# Solarregler.net
KiCad netlist of a schematic drawn in EAGLE
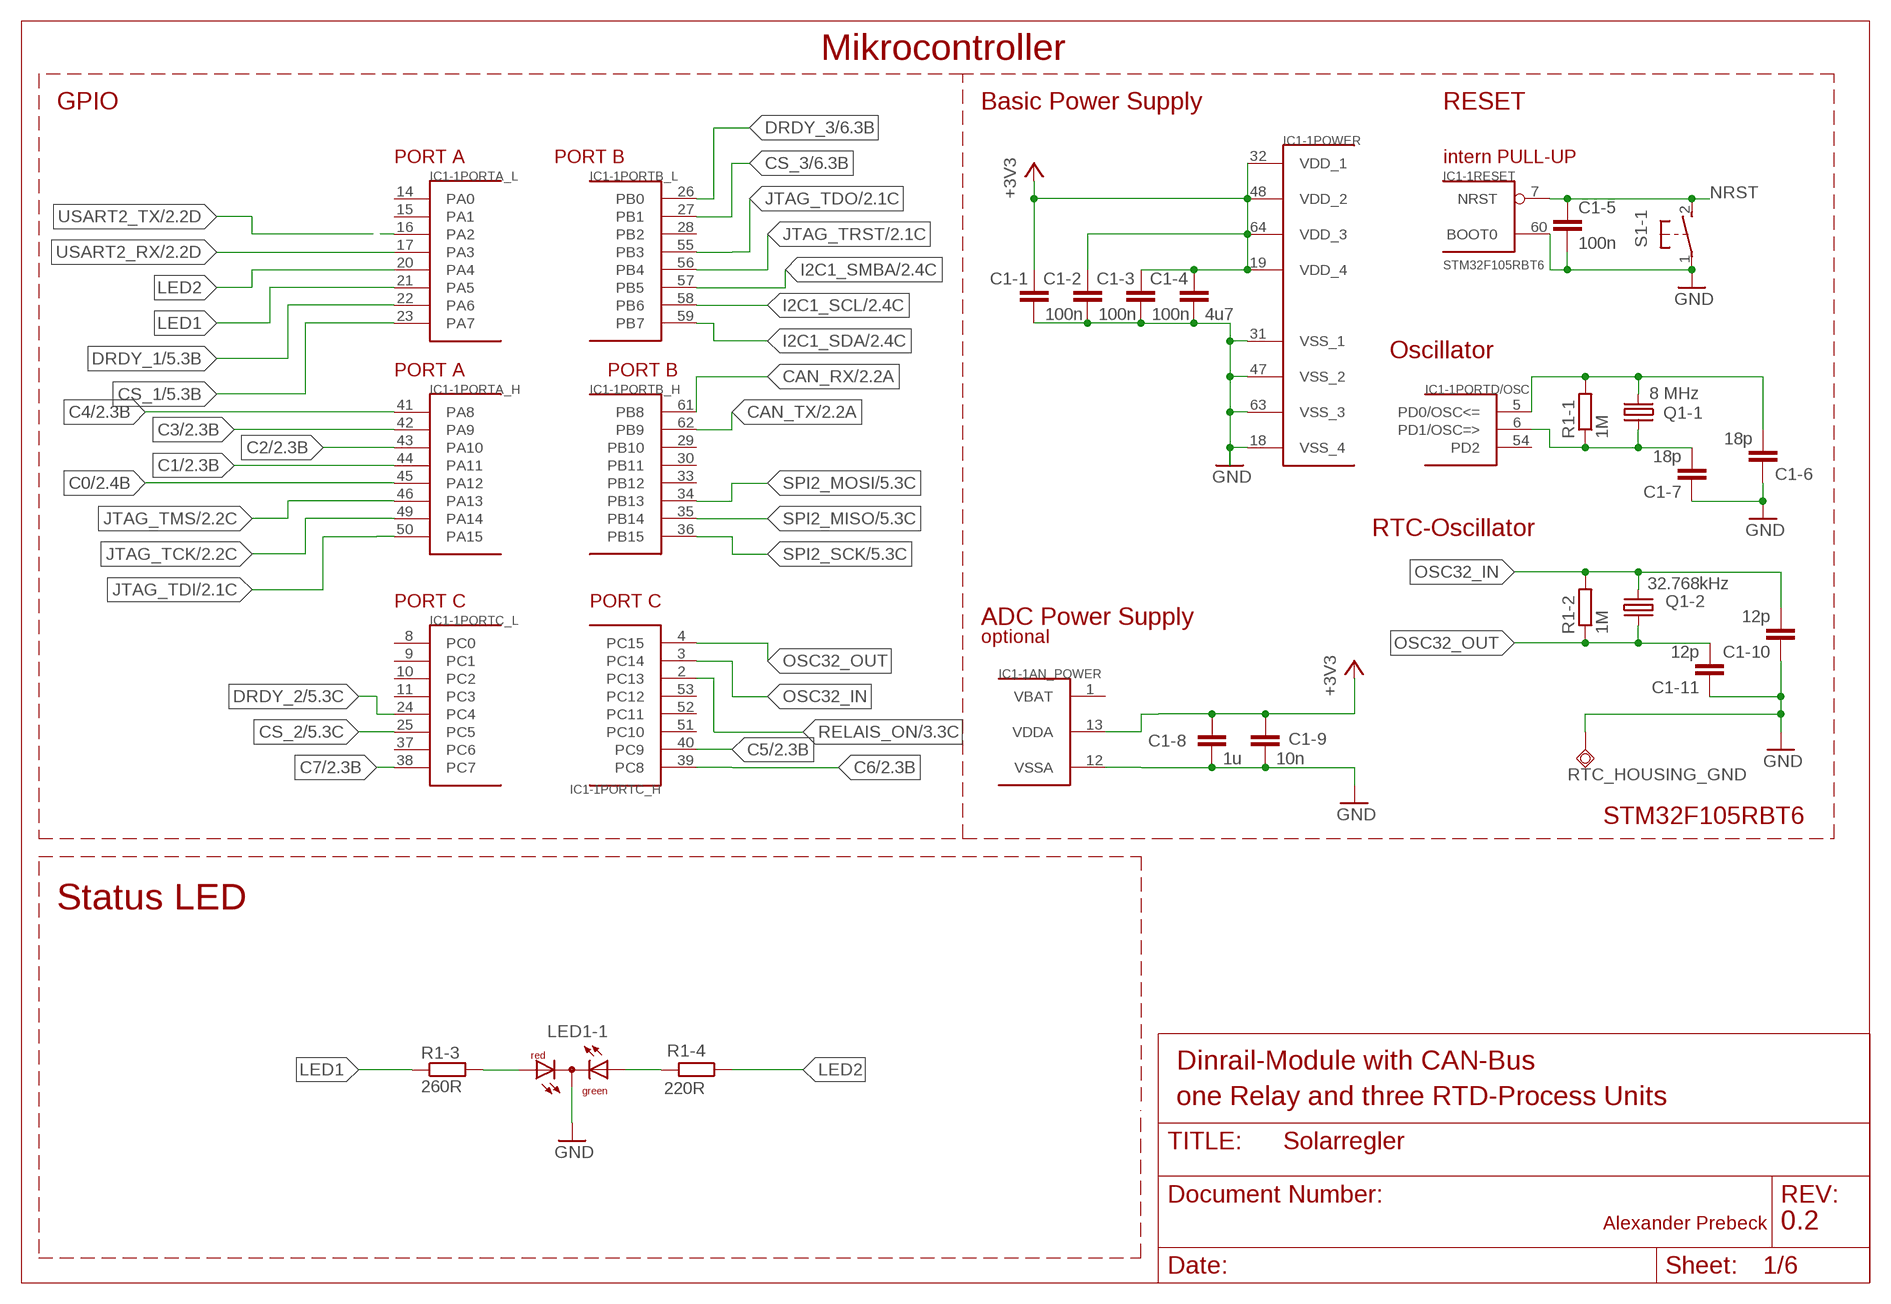
[diagram p0: schematic, sheet 1]
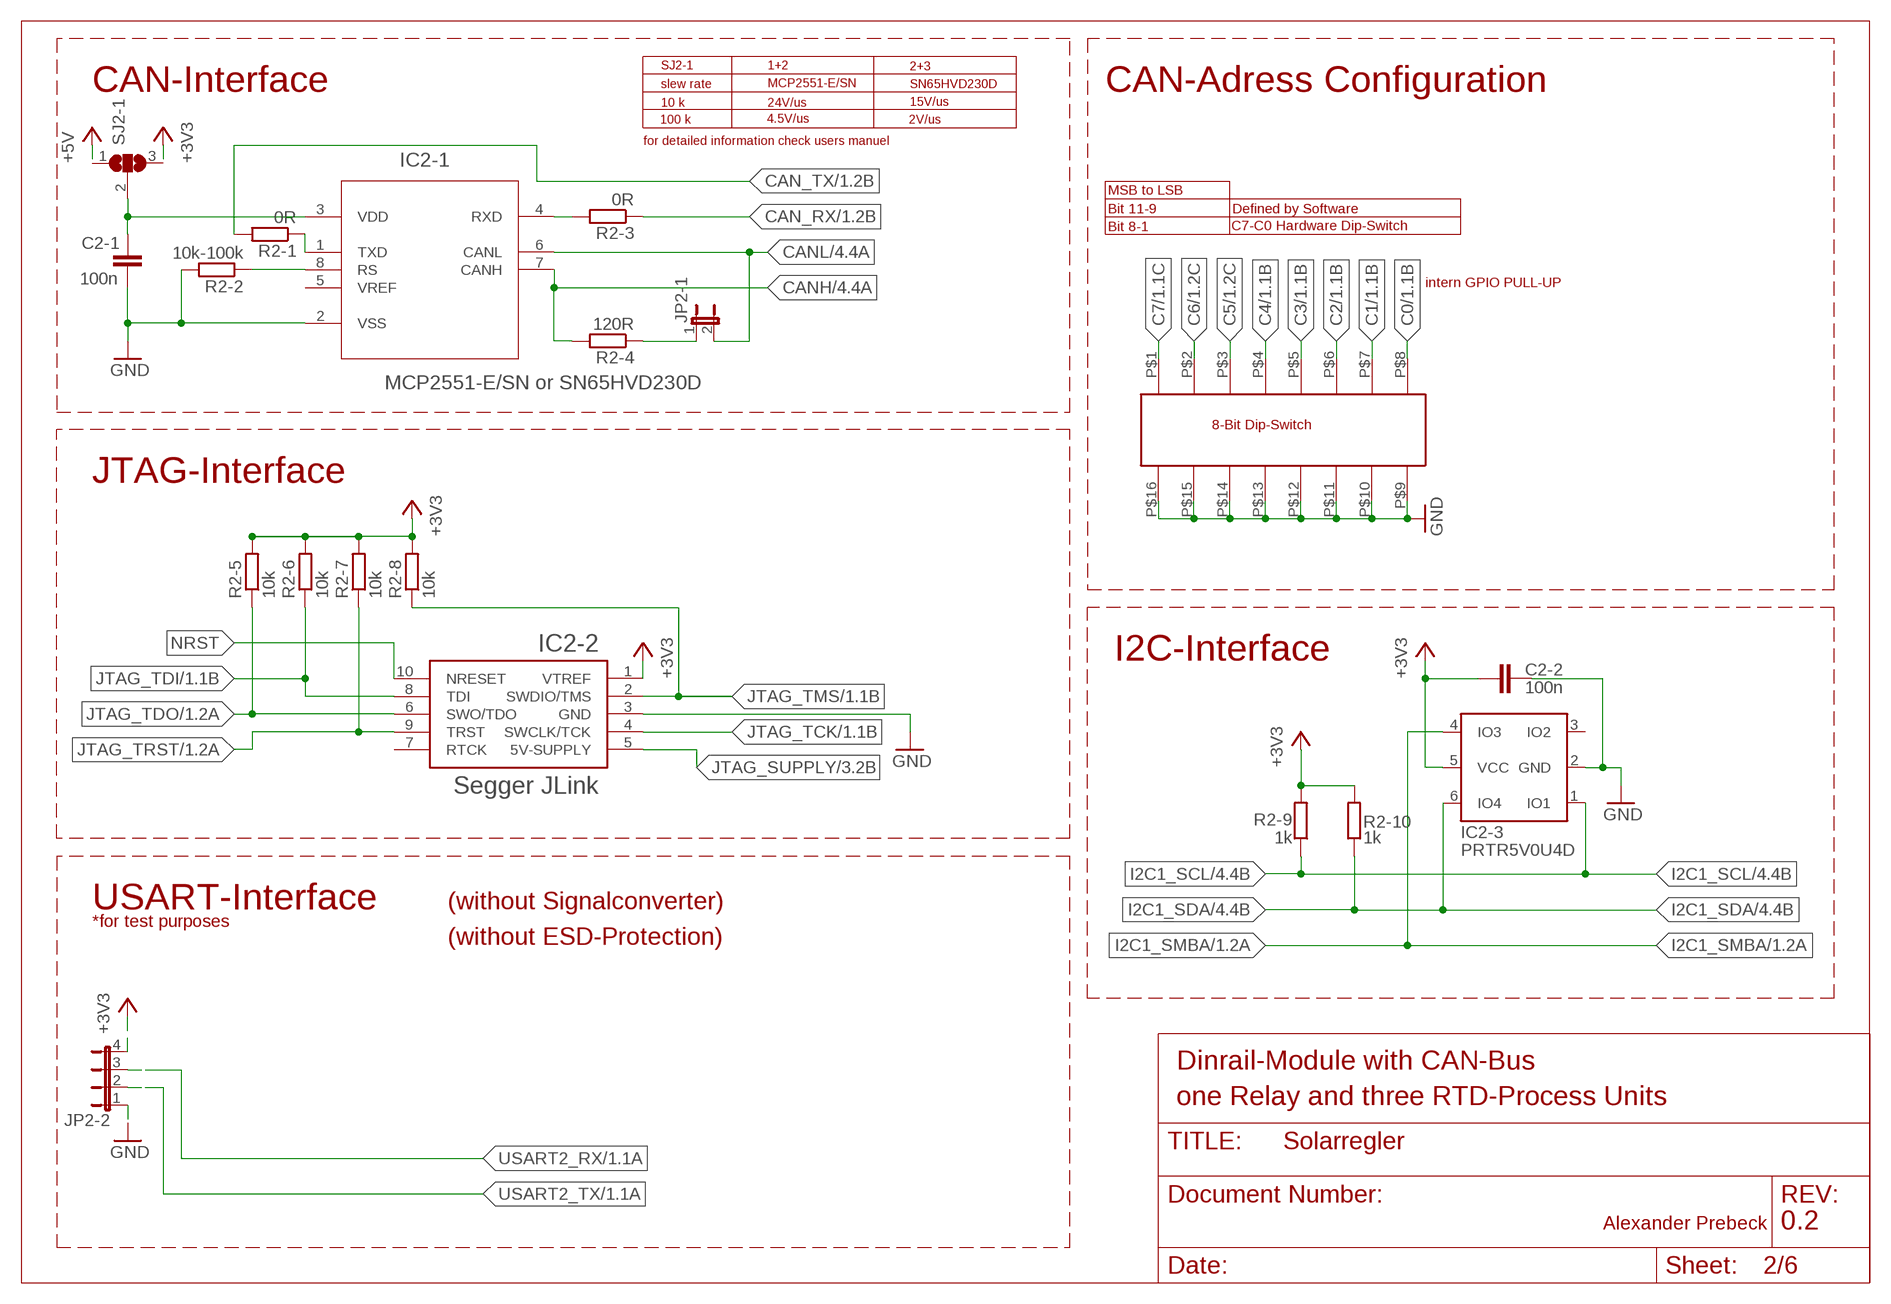
[diagram p1: schematic, sheet 2]
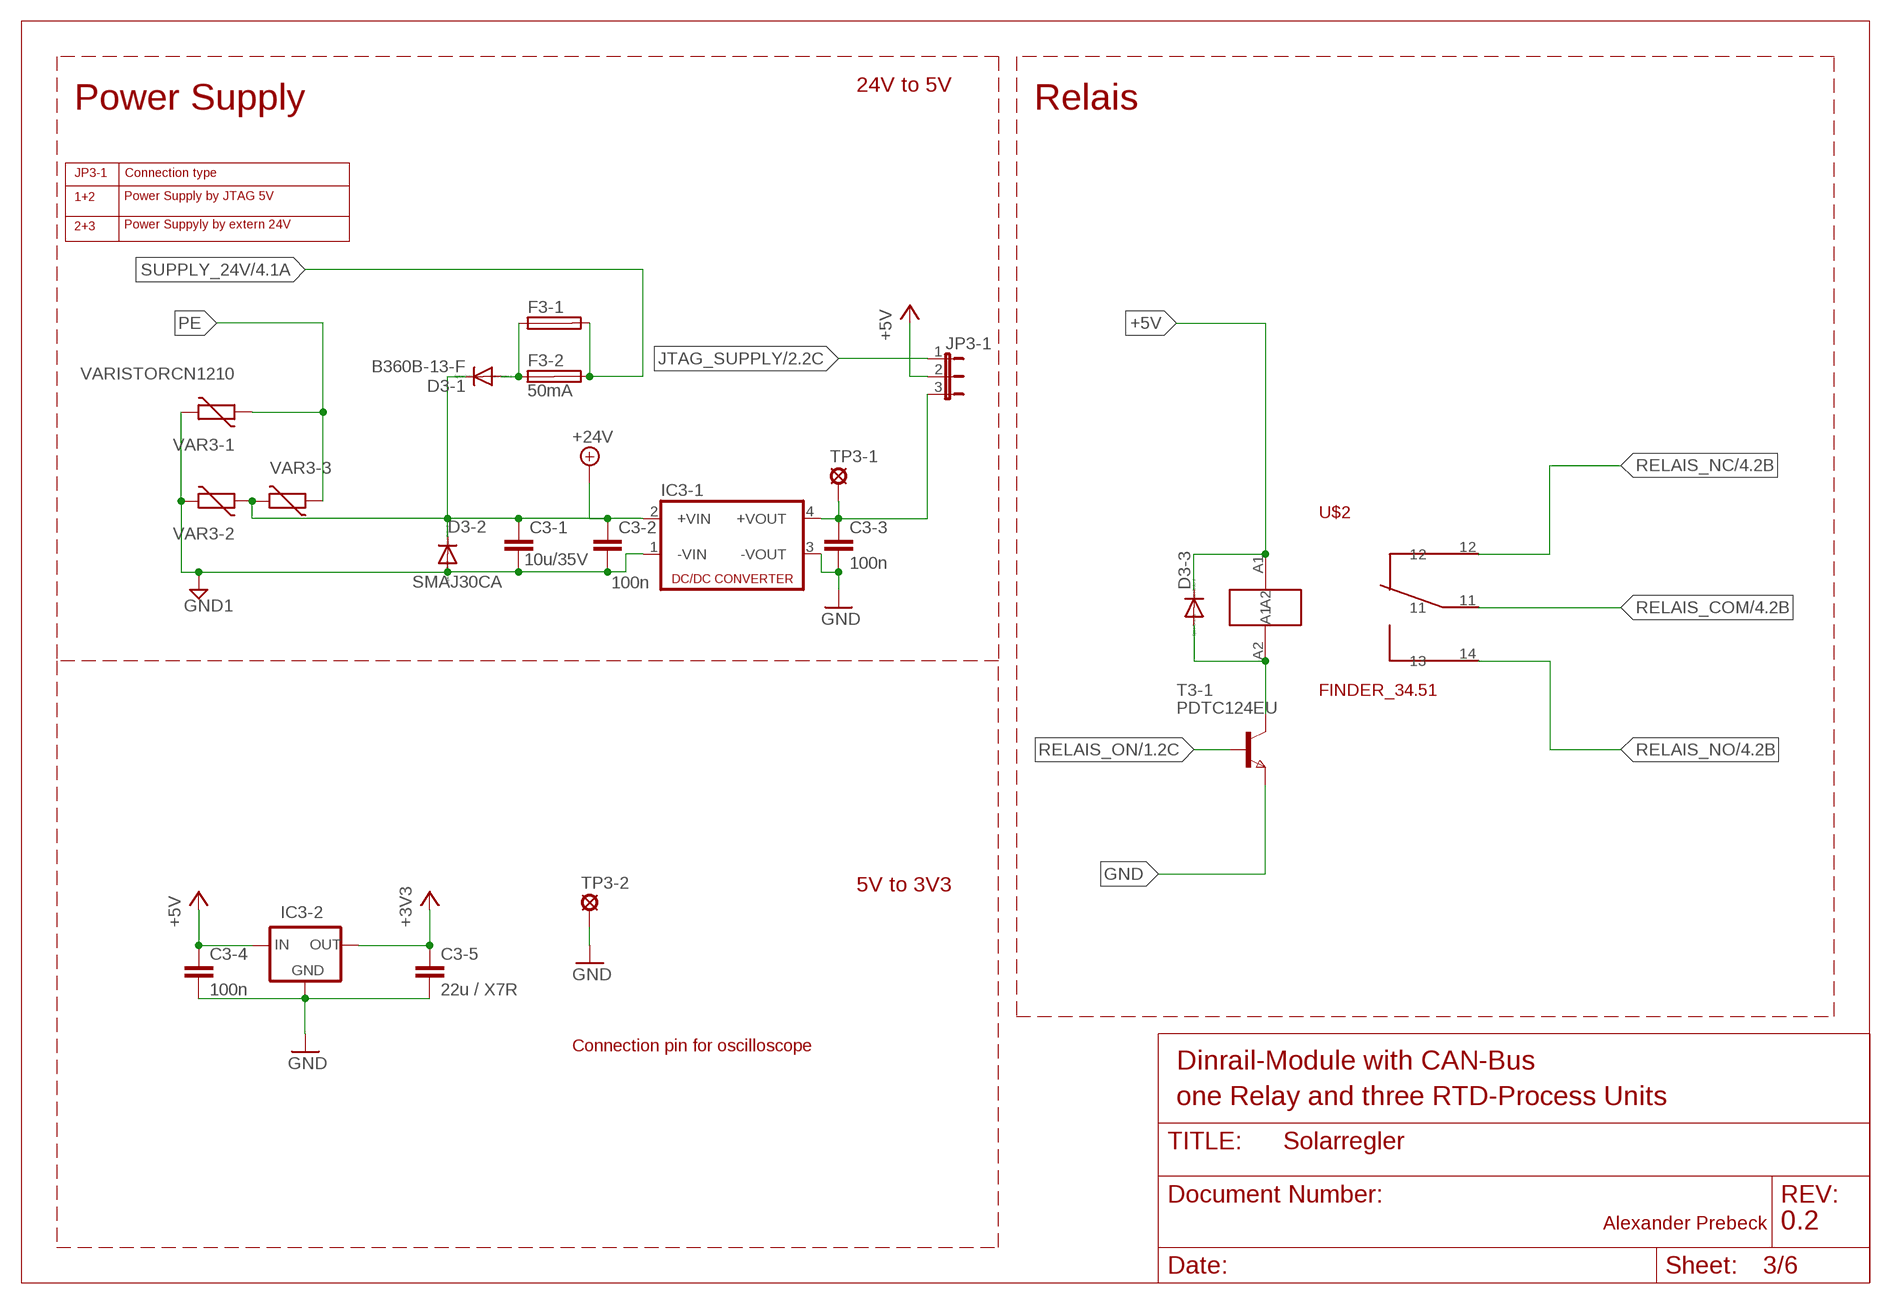
[diagram p2: schematic, sheet 3]
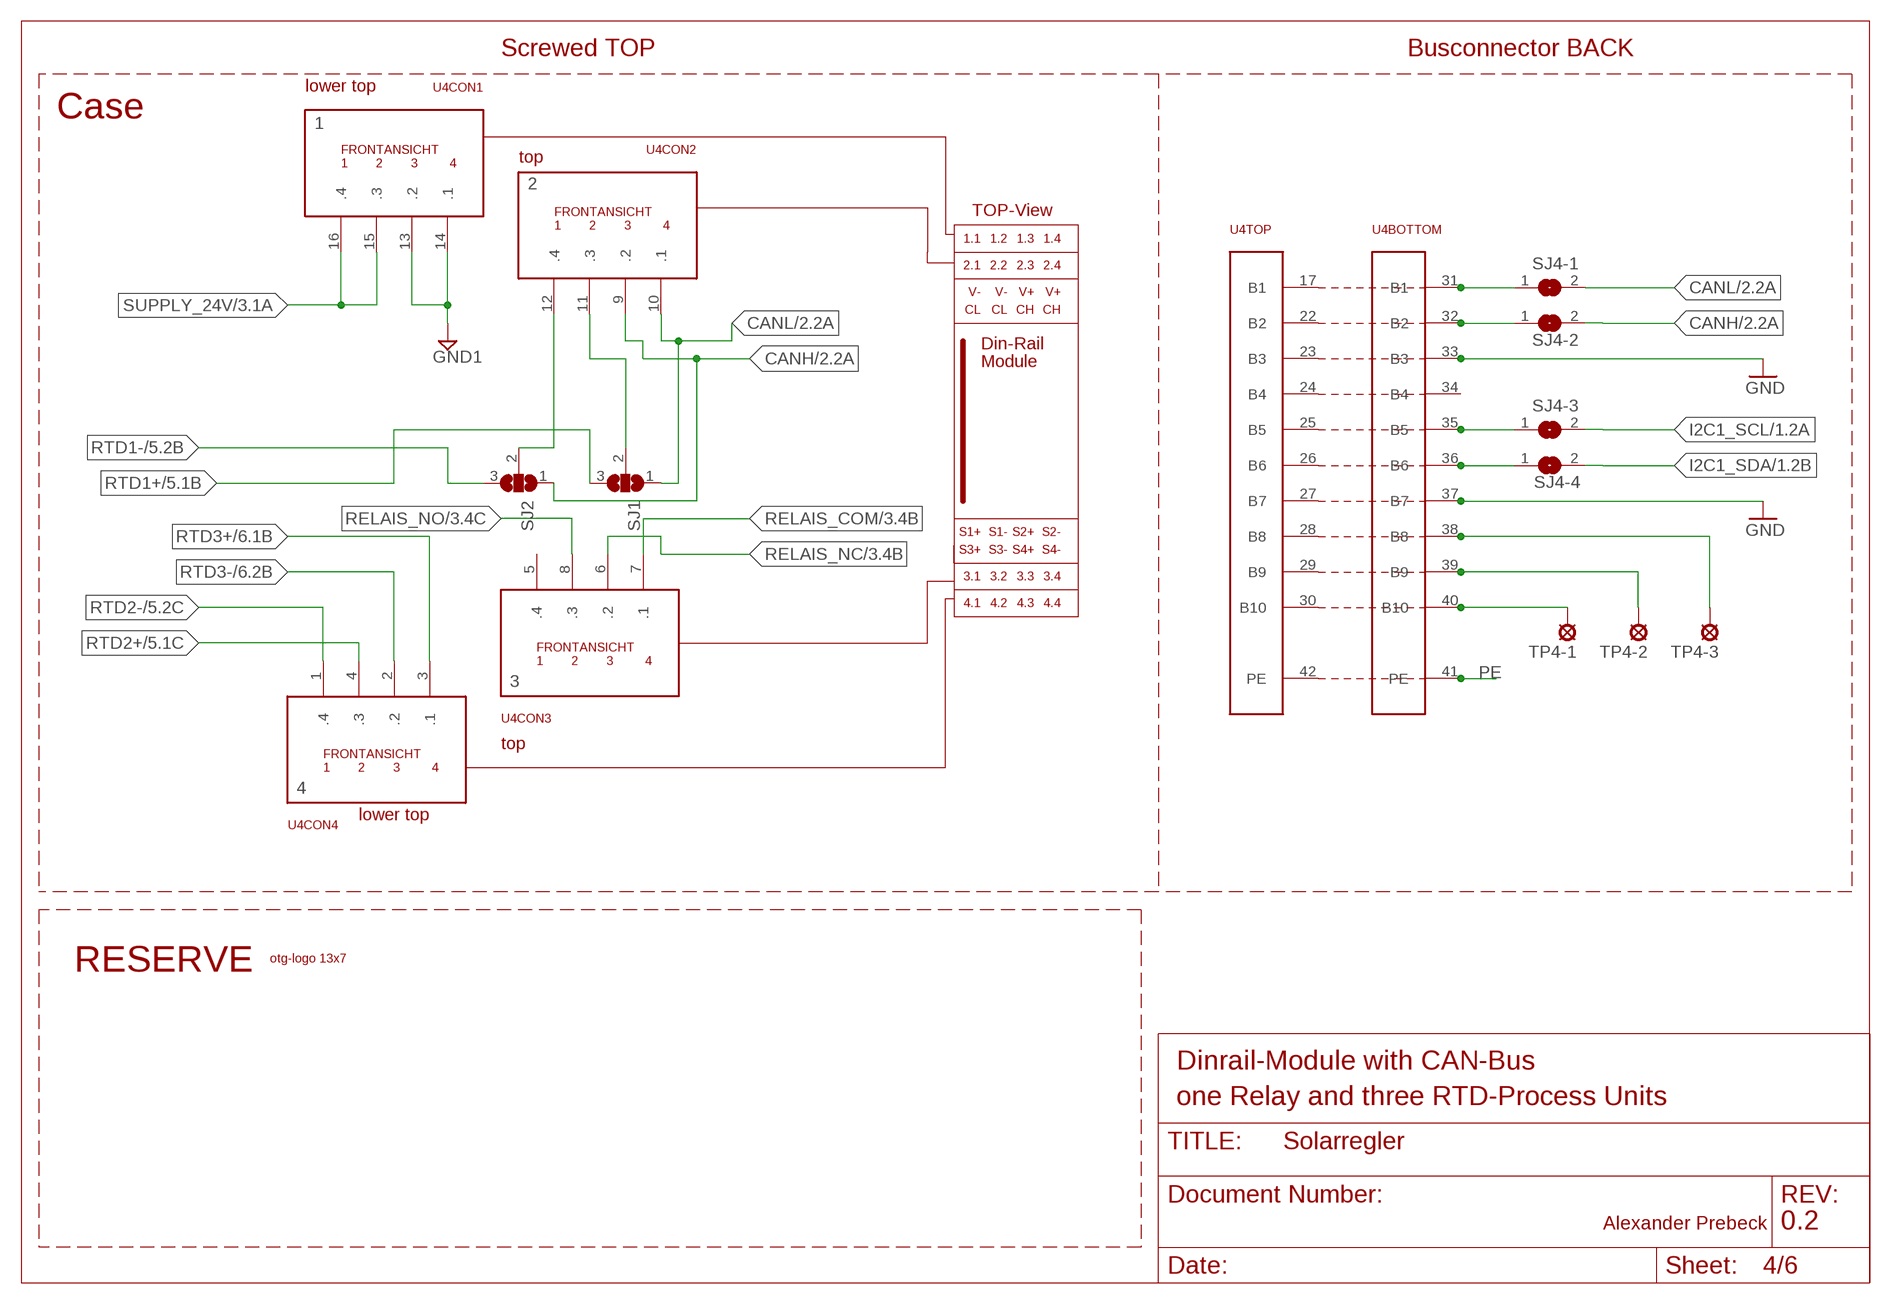
[diagram p3: schematic, sheet 4]
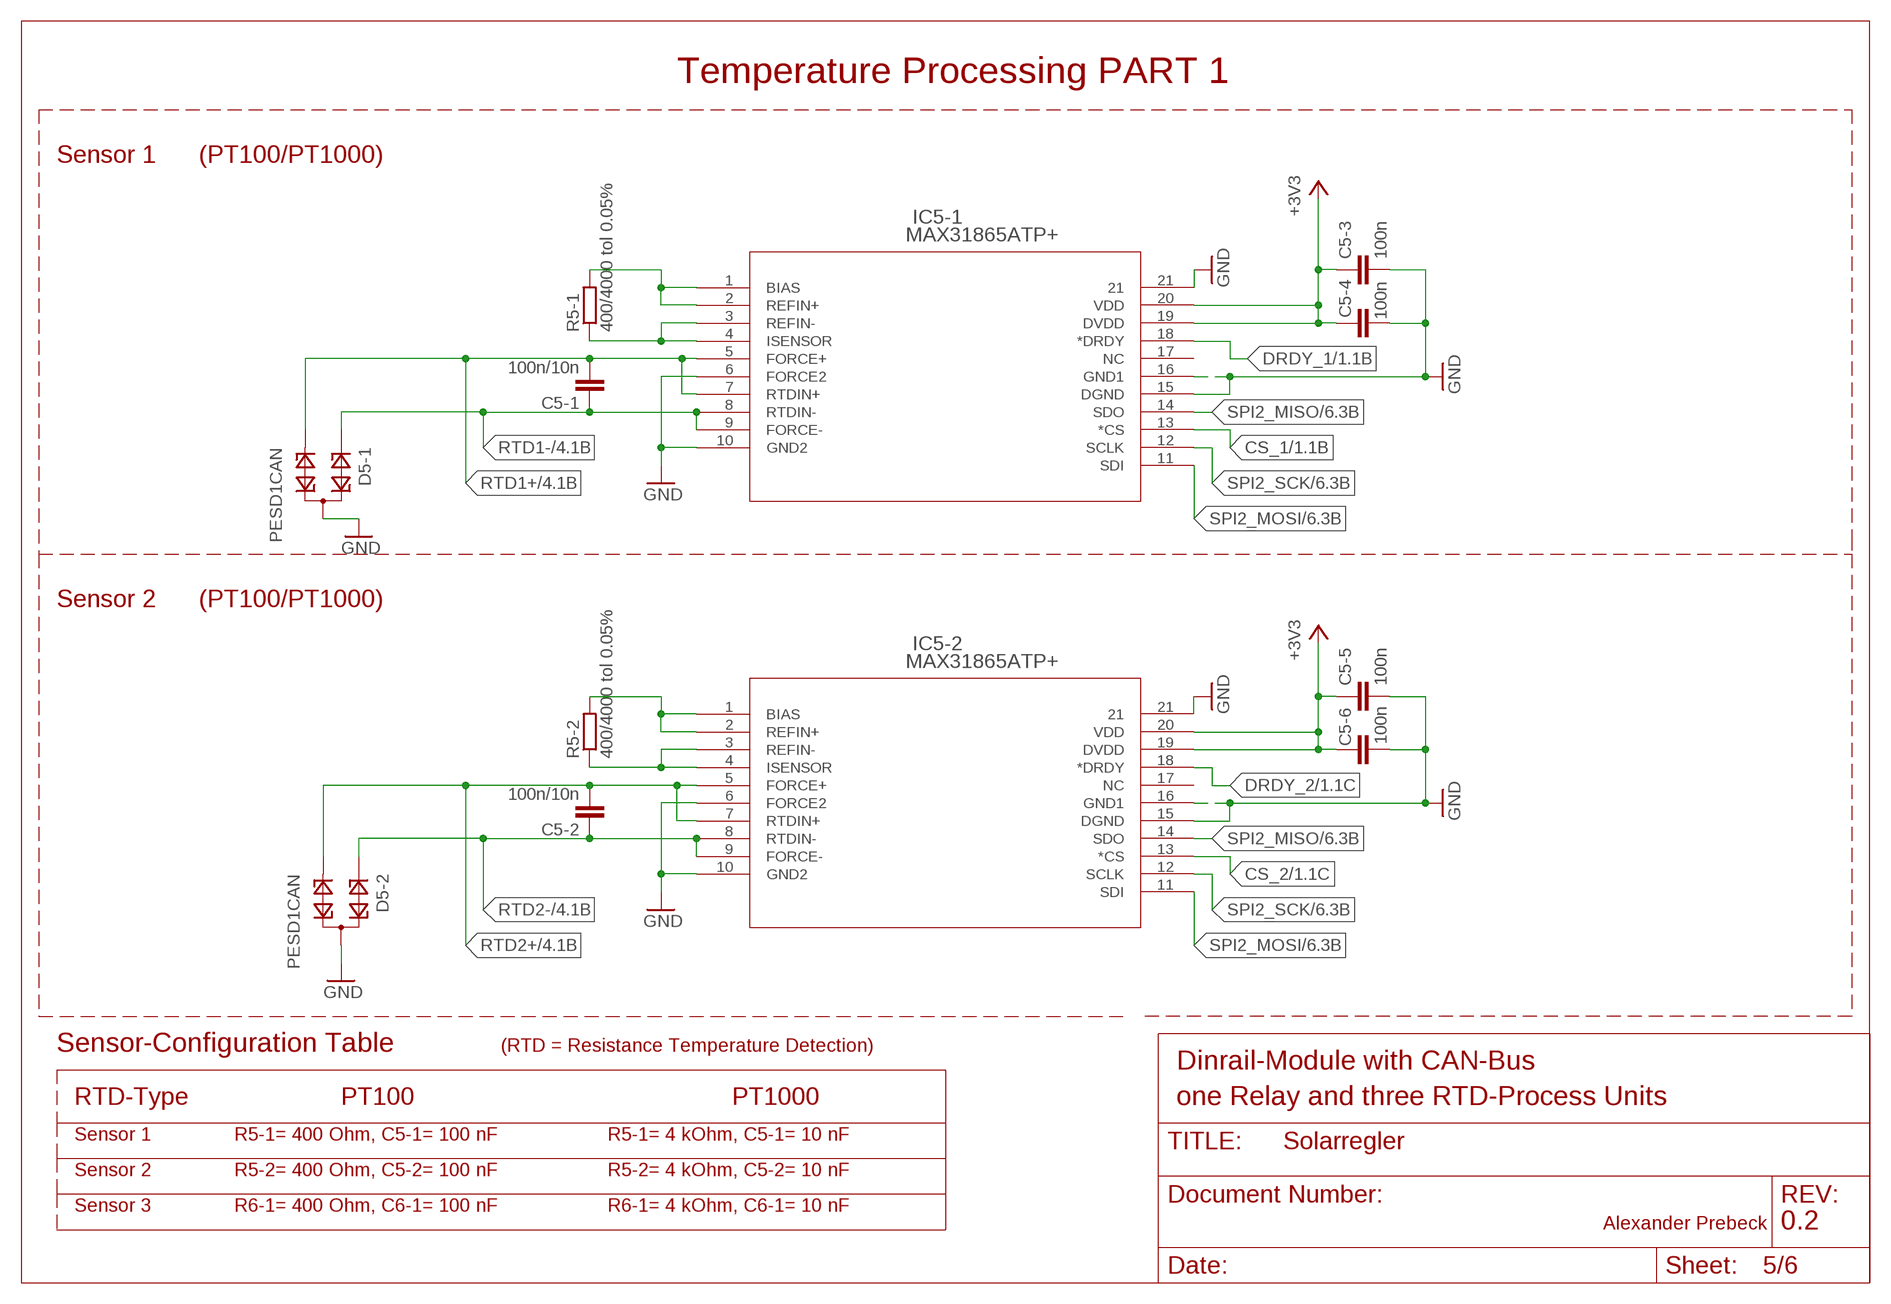
[diagram p4: schematic, sheet 5]
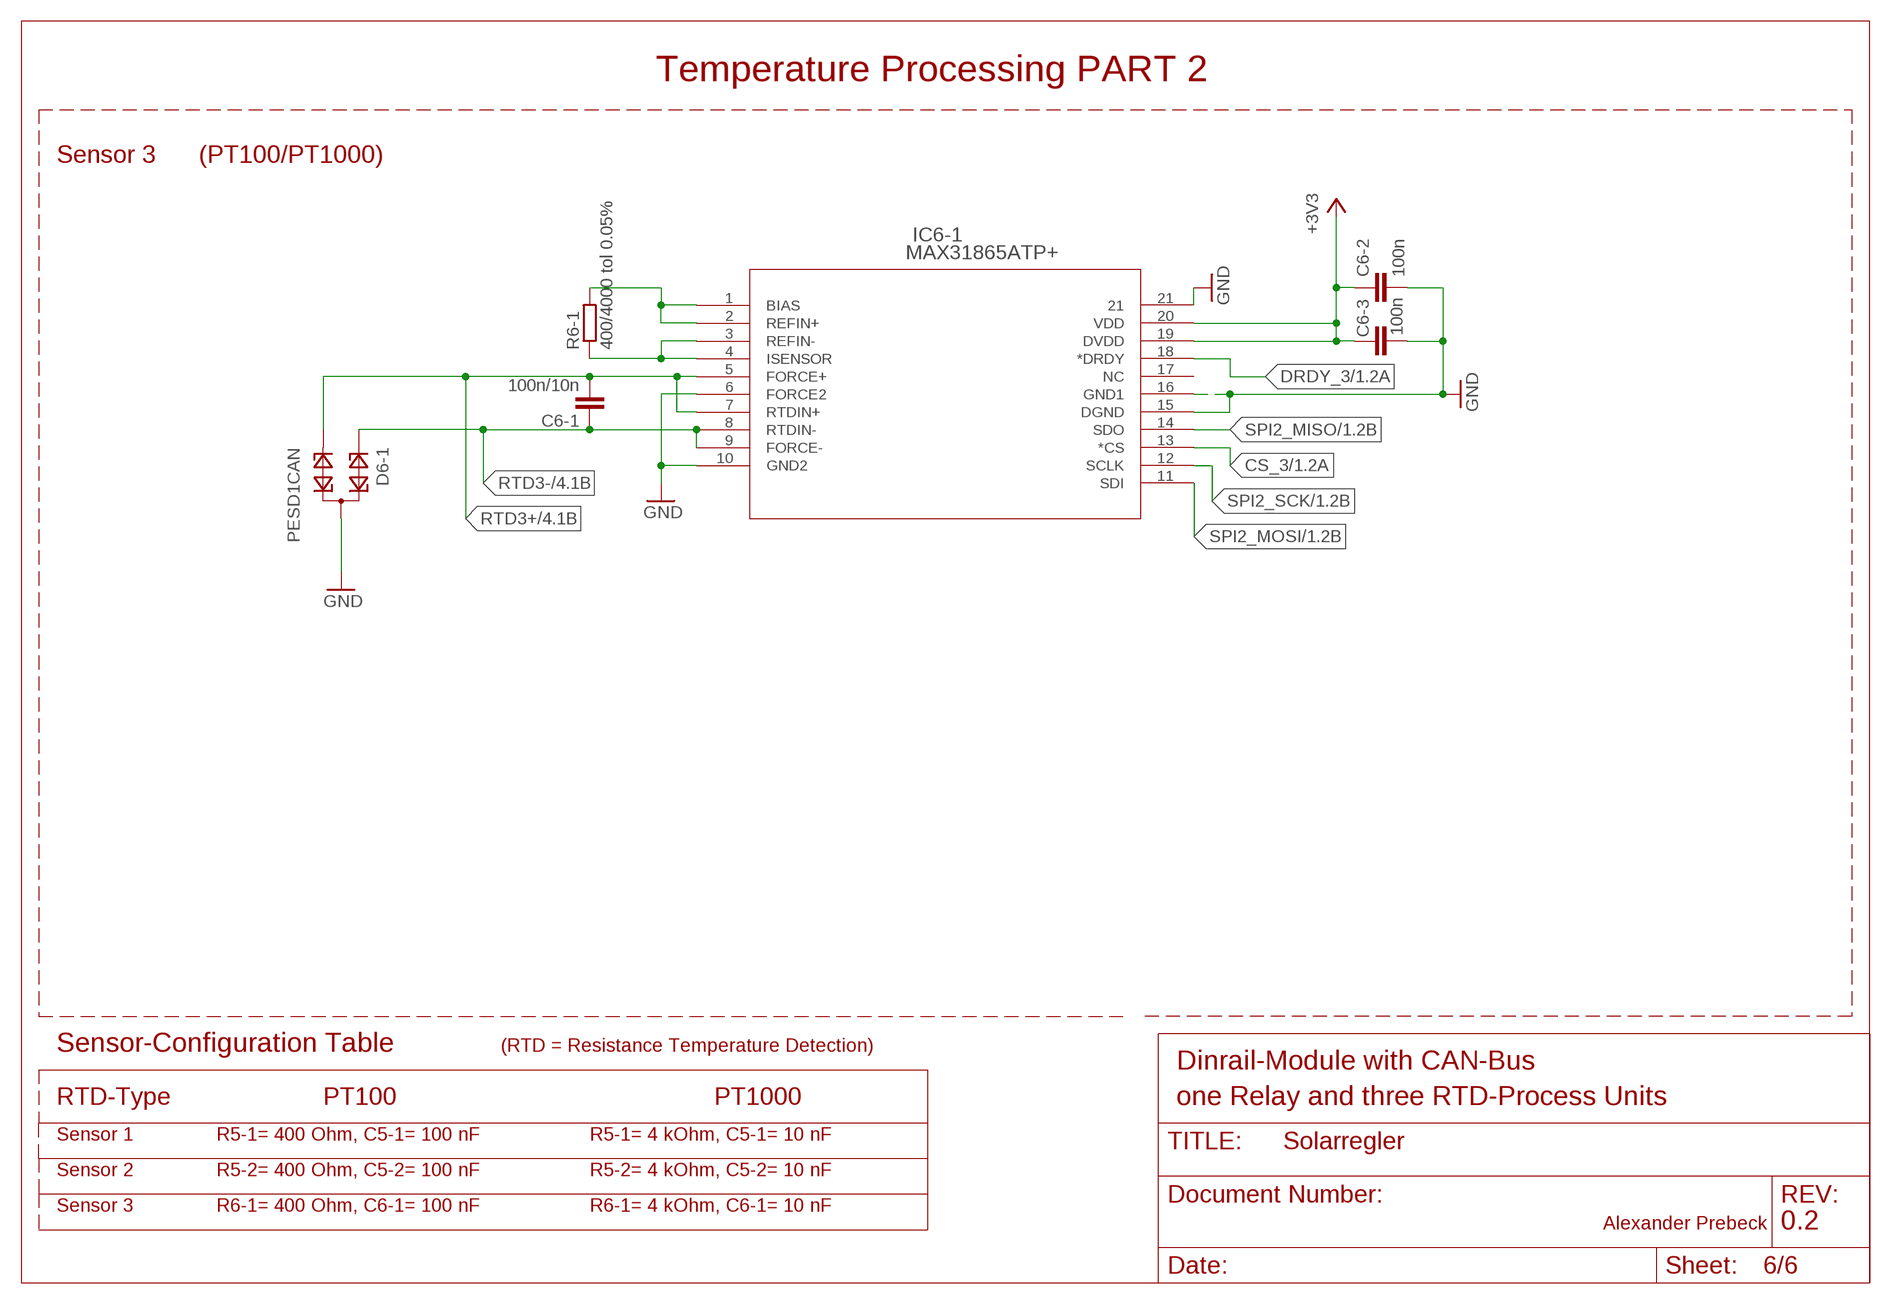
[diagram p5: schematic, sheet 6]

(export (version "E")
  (design (tool "Eeschema 10.0.6"))
  (components
    (comp (ref "C3-1")
      (value "10u/35V")
      (footprint "eagle-import:C0805")
      (fields (field (name "MF") "MURATA") (field (name "MPN") "GRM31CC8YA106KA12L"))
      (libsource (lib "eagle-import") (part "C-EUC0805"))
    )
    (comp (ref "C3-2")
      (value "100n")
      (footprint "eagle-import:C0603")
      (fields (field (name "MF") "KEMET") (field (name "MPN") "C0805C104K1RAC AUTO"))
      (libsource (lib "eagle-import") (part "C-EUC0603"))
    )
    (comp (ref "C3-3")
      (value "100n")
      (footprint "eagle-import:C0603")
      (fields (field (name "MF") "KEMET") (field (name "MPN") "C0805C104K1RAC AUTO"))
      (libsource (lib "eagle-import") (part "C-EUC0603"))
    )
    (comp (ref "C3-4")
      (value "100n")
      (footprint "eagle-import:C0603")
      (fields (field (name "MF") "KEMET") (field (name "MPN") "C0805C104K1RAC AUTO"))
      (libsource (lib "eagle-import") (part "C-EUC0603"))
    )
    (comp (ref "C3-5")
      (value "22u / X7R")
      (footprint "eagle-import:C0805")
      (fields (field (name "MF") "KEMET") (field (name "MPN") "C0805C104K1RAC AUTO"))
      (libsource (lib "eagle-import") (part "C-EUC0805"))
    )
    (comp (ref "D3-1")
      (value "B360B-13-F")
      (footprint "eagle-import:SMB")
      (fields (field (name "MF") "DIODES INC."))
      (libsource (lib "eagle-import") (part "DIODE-SMB"))
    )
    (comp (ref "D3-2")
      (value "SMAJ30CA")
      (footprint "eagle-import:DO214AA")
      (fields (field (name "MF") "MULTICOMP"))
      (libsource (lib "eagle-import") (part "DIODE-DO214AA"))
    )
    (comp (ref "D3-3")
      (value "DIODE-SMB")
      (footprint "eagle-import:SMB")
      (libsource (lib "eagle-import") (part "DIODE-SMB"))
    )
    (comp (ref "F3-1")
      (value "FUSE_1210")
      (footprint "eagle-import:1210")
      (libsource (lib "eagle-import") (part "FUSE_1210"))
    )
    (comp (ref "F3-2")
      (value "50mA")
      (footprint "eagle-import:SHK20Q")
      (fields
        (field (name "MF") "SCHURTER")
        (field (name "MPN") "0031.8201")
        (field (name "OC_FARNELL") "1162740")
      )
      (libsource (lib "eagle-import") (part "SHK20Q"))
    )
    (comp (ref "IC3-1")
      (value "SIM1")
      (footprint "eagle-import:4SIL")
      (fields (field (name "MF") "XP POWER") (field (name "MPN") "IE2405S"))
      (libsource (lib "eagle-import") (part "SIM1"))
    )
    (comp (ref "IC3-2")
      (value "MIC5209")
      (footprint "eagle-import:SOT223")
      (fields (field (name "MF") "MICREL SEMICONDUCTOR") (field (name "MPN") "MIC5209-3.3YS TR"))
      (libsource (lib "eagle-import") (part "MIC5209"))
    )
    (comp (ref "JP3-1")
      (value "JP2E")
      (footprint "eagle-import:JP2")
      (libsource (lib "eagle-import") (part "JP2E"))
    )
    (comp (ref "T3-1")
      (value "PDTC124EU")
      (footprint "eagle-import:SOT323")
      (fields (field (name "MPN") "DSS4160U-7"))
      (libsource (lib "eagle-import") (part "NPNSOT323"))
    )
    (comp (ref "TP3-1")
      (value "LSP10")
      (footprint "eagle-import:LSP10")
      (libsource (lib "eagle-import") (part "LSP10"))
    )
    (comp (ref "TP3-2")
      (value "LSP10")
      (footprint "eagle-import:LSP10")
      (libsource (lib "eagle-import") (part "LSP10"))
    )
    (comp (ref "U$2")
      (value "FINDER_34.51")
      (footprint "eagle-import:SERIES_34")
      (libsource (lib "eagle-import") (part "FINDER_34.51"))
    )
    (comp (ref "VAR3-1")
      (value "VARISTORCN1210")
      (footprint "eagle-import:CT_CN1210")
      (fields (field (name "MF") "AVX") (field (name "MPN") "VC121030H620DP"))
      (libsource (lib "eagle-import") (part "VARISTORCN1210"))
    )
    (comp (ref "VAR3-2")
      (value "VARISTORCN1210")
      (footprint "eagle-import:CT_CN1210")
      (fields (field (name "MF") "AVX") (field (name "MPN") "VC121030H620DP"))
      (libsource (lib "eagle-import") (part "VARISTORCN1210"))
    )
    (comp (ref "VAR3-3")
      (value "VARISTORCN1210")
      (footprint "eagle-import:CT_CN1210")
      (fields (field (name "MF") "AVX") (field (name "MPN") "VC121030H620DP"))
      (libsource (lib "eagle-import") (part "VARISTORCN1210"))
    )
    (comp (ref "C5-1")
      (value "100n/10n")
      (footprint "eagle-import:C0603")
      (libsource (lib "eagle-import") (part "C-EUC0603"))
    )
    (comp (ref "C5-2")
      (value "100n/10n")
      (footprint "eagle-import:C0603")
      (libsource (lib "eagle-import") (part "C-EUC0603"))
    )
    (comp (ref "C5-3")
      (value "100n")
      (footprint "eagle-import:C0603")
      (libsource (lib "eagle-import") (part "C-EUC0603"))
    )
    (comp (ref "C5-4")
      (value "100n")
      (footprint "eagle-import:C0603")
      (libsource (lib "eagle-import") (part "C-EUC0603"))
    )
    (comp (ref "C5-5")
      (value "100n")
      (footprint "eagle-import:C0603")
      (libsource (lib "eagle-import") (part "C-EUC0603"))
    )
    (comp (ref "C5-6")
      (value "100n")
      (footprint "eagle-import:C0603")
      (libsource (lib "eagle-import") (part "C-EUC0603"))
    )
    (comp (ref "D5-1")
      (value "PESD1CAN")
      (footprint "eagle-import:SOT23")
      (libsource (lib "eagle-import") (part "PESD1CAN"))
    )
    (comp (ref "D5-2")
      (value "PESD1CAN")
      (footprint "eagle-import:SOT23")
      (libsource (lib "eagle-import") (part "PESD1CAN"))
    )
    (comp (ref "IC5-1")
      (value "MAX31865ATP+")
      (footprint "eagle-import:21-0140L_T2055-5")
      (libsource (lib "eagle-import") (part "MAX31865ATP+"))
    )
    (comp (ref "IC5-2")
      (value "MAX31865ATP+")
      (footprint "eagle-import:21-0140L_T2055-5")
      (libsource (lib "eagle-import") (part "MAX31865ATP+"))
    )
    (comp (ref "R5-1")
      (value "400/4000 tol 0.05%")
      (footprint "eagle-import:R0603")
      (libsource (lib "eagle-import") (part "R-EU_R0603"))
    )
    (comp (ref "R5-2")
      (value "400/4000 tol 0.05%")
      (footprint "eagle-import:R0603")
      (libsource (lib "eagle-import") (part "R-EU_R0603"))
    )
    (comp (ref "C1-1")
      (value "100n")
      (footprint "eagle-import:C0603")
      (fields (field (name "MF") "KEMET") (field (name "MPN") "C0805C104K1RAC AUTO"))
      (libsource (lib "eagle-import") (part "C-EUC0603"))
    )
    (comp (ref "C1-2")
      (value "100n")
      (footprint "eagle-import:C0603")
      (fields (field (name "MF") "KEMET") (field (name "MPN") "C0805C104K1RAC AUTO"))
      (libsource (lib "eagle-import") (part "C-EUC0603"))
    )
    (comp (ref "C1-3")
      (value "100n")
      (footprint "eagle-import:C0603")
      (fields (field (name "MF") "KEMET") (field (name "MPN") "C0805C104K1RAC AUTO"))
      (libsource (lib "eagle-import") (part "C-EUC0603"))
    )
    (comp (ref "C1-4")
      (value "4u7")
      (footprint "eagle-import:C1206")
      (fields (field (name "MF") "MURATA") (field (name "MPN") "GRM21BR61A475KA73L"))
      (libsource (lib "eagle-import") (part "C-EUC1206"))
    )
    (comp (ref "C1-5")
      (value "100n")
      (footprint "eagle-import:C0603")
      (fields (field (name "MF") "KEMET") (field (name "MPN") "C0805C104K1RAC AUTO"))
      (libsource (lib "eagle-import") (part "C-EUC0603"))
    )
    (comp (ref "C1-6")
      (value "18p")
      (footprint "eagle-import:C0603")
      (fields (field (name "MF") "KEMET") (field (name "MPN") "C0805C270J5GACTU"))
      (libsource (lib "eagle-import") (part "C-EUC0603"))
    )
    (comp (ref "C1-7")
      (value "18p")
      (footprint "eagle-import:C0603")
      (fields (field (name "MF") "KEMET") (field (name "MPN") "C0805C270J5GACTU"))
      (libsource (lib "eagle-import") (part "C-EUC0603"))
    )
    (comp (ref "C1-8")
      (value "1u")
      (footprint "eagle-import:C0805")
      (fields (field (name "MF") "MURATA") (field (name "MPN") "GRM21BR71E105KA99L"))
      (libsource (lib "eagle-import") (part "C-EUC0805"))
    )
    (comp (ref "C1-9")
      (value "10n")
      (footprint "eagle-import:C0603")
      (fields (field (name "MF") "MULTICOMP") (field (name "MPN") "MC0805B103K500CT"))
      (libsource (lib "eagle-import") (part "C-EUC0603"))
    )
    (comp (ref "C1-10")
      (value "12p")
      (footprint "eagle-import:C0603")
      (fields (field (name "MF") "KEMET") (field (name "MPN") "C0805C270J5GACTU"))
      (libsource (lib "eagle-import") (part "C-EUC0603"))
    )
    (comp (ref "C1-11")
      (value "12p")
      (footprint "eagle-import:C0603")
      (fields (field (name "MF") "KEMET") (field (name "MPN") "C0805C270J5GACTU"))
      (libsource (lib "eagle-import") (part "C-EUC0603"))
    )
    (comp (ref "IC1-1")
      (value "STM32F105RBT6")
      (footprint "eagle-import:TQFP64")
      (libsource (lib "eagle-import") (part "STM32F10XRXT6"))
    )
    (comp (ref "LED1-1")
      (value "DUOLED-RG-C")
      (footprint "eagle-import:DUOLED-C-5MM")
      (libsource (lib "eagle-import") (part "DUOLED-RG-C"))
    )
    (comp (ref "Q1-1")
      (value "8 MHz")
      (footprint "eagle-import:SMD_QUARZ_6X3.5MM")
      (libsource (lib "eagle-import") (part "SMD_QUARZ_6X3.5MM"))
    )
    (comp (ref "Q1-2")
      (value "32.768kHz")
      (footprint "eagle-import:THROUGH_HOLE_QUARZ_RTC")
      (libsource (lib "eagle-import") (part "QUARZ_RTC_TH"))
    )
    (comp (ref "R1-1")
      (value "1M")
      (footprint "eagle-import:R0603")
      (libsource (lib "eagle-import") (part "R-EU_R0603"))
    )
    (comp (ref "R1-2")
      (value "1M")
      (footprint "eagle-import:R0603")
      (libsource (lib "eagle-import") (part "R-EU_R0603"))
    )
    (comp (ref "R1-3")
      (value "260R")
      (footprint "eagle-import:R0603")
      (libsource (lib "eagle-import") (part "R-EU_R0603"))
    )
    (comp (ref "R1-4")
      (value "220R")
      (footprint "eagle-import:R0603")
      (libsource (lib "eagle-import") (part "R-EU_R0603"))
    )
    (comp (ref "RTC_HOUSING_GND")
      (value "TPSQTP20SQ")
      (footprint "eagle-import:TP20SQ")
      (libsource (lib "eagle-import") (part "TPSQTP20SQ"))
    )
    (comp (ref "S1-1")
      (value "31-XX")
      (footprint "eagle-import:B3F-31XX")
      (fields (field (name "MPN") "B3F-3100") (field (name "MF") "OMRON ELECTRONIC COMPONENTS"))
      (libsource (lib "eagle-import") (part "31-XX"))
    )
    (comp (ref "SJ1")
      (value "SJ2W")
      (footprint "eagle-import:SJ_2")
      (libsource (lib "eagle-import") (part "SJ2W"))
    )
    (comp (ref "SJ2")
      (value "SJ2W")
      (footprint "eagle-import:SJ_2")
      (libsource (lib "eagle-import") (part "SJ2W"))
    )
    (comp (ref "SJ4-1")
      (value "SJW")
      (footprint "eagle-import:SJW")
      (libsource (lib "eagle-import") (part "SJW"))
    )
    (comp (ref "SJ4-2")
      (value "SJW")
      (footprint "eagle-import:SJW")
      (libsource (lib "eagle-import") (part "SJW"))
    )
    (comp (ref "SJ4-3")
      (value "SJW")
      (footprint "eagle-import:SJW")
      (libsource (lib "eagle-import") (part "SJW"))
    )
    (comp (ref "SJ4-4")
      (value "SJW")
      (footprint "eagle-import:SJW")
      (libsource (lib "eagle-import") (part "SJW"))
    )
    (comp (ref "TP4-1")
      (value "LSP10")
      (footprint "eagle-import:LSP10")
      (libsource (lib "eagle-import") (part "LSP10"))
    )
    (comp (ref "TP4-2")
      (value "LSP10")
      (footprint "eagle-import:LSP10")
      (libsource (lib "eagle-import") (part "LSP10"))
    )
    (comp (ref "TP4-3")
      (value "LSP10")
      (footprint "eagle-import:LSP10")
      (libsource (lib "eagle-import") (part "LSP10"))
    )
    (comp (ref "U$1")
      (value "OTH-LOGO13X7")
      (footprint "eagle-import:OTH-LOGO_SMALL")
      (libsource (lib "eagle-import") (part "OTH-LOGO13X7"))
    )
    (comp (ref "U4")
      (value "HUTSCHIENE_DEV")
      (footprint "eagle-import:HUTSCHIENE")
      (fields (field (name "OC_FARNELL") "unknown"))
      (libsource (lib "eagle-import") (part "HUTSCHIENE_DEV"))
    )
    (comp (ref "C6-1")
      (value "100n/10n")
      (footprint "eagle-import:C0603")
      (libsource (lib "eagle-import") (part "C-EUC0603"))
    )
    (comp (ref "C6-2")
      (value "100n")
      (footprint "eagle-import:C0603")
      (libsource (lib "eagle-import") (part "C-EUC0603"))
    )
    (comp (ref "C6-3")
      (value "100n")
      (footprint "eagle-import:C0603")
      (libsource (lib "eagle-import") (part "C-EUC0603"))
    )
    (comp (ref "D6-1")
      (value "PESD1CAN")
      (footprint "eagle-import:SOT23")
      (libsource (lib "eagle-import") (part "PESD1CAN"))
    )
    (comp (ref "IC6-1")
      (value "MAX31865ATP+")
      (footprint "eagle-import:21-0140L_T2055-5")
      (libsource (lib "eagle-import") (part "MAX31865ATP+"))
    )
    (comp (ref "R6-1")
      (value "400/4000 tol 0.05%")
      (footprint "eagle-import:R0603")
      (libsource (lib "eagle-import") (part "R-EU_R0603"))
    )
    (comp (ref "C2-1")
      (value "100n")
      (footprint "eagle-import:C0603")
      (fields (field (name "MF") "KEMET") (field (name "MPN") "C0805C104K1RAC AUTO"))
      (libsource (lib "eagle-import") (part "C-EUC0603"))
    )
    (comp (ref "C2-2")
      (value "100n")
      (footprint "eagle-import:C0603")
      (fields (field (name "MF") "KEMET") (field (name "MPN") "C0805C104K1RAC AUTO"))
      (libsource (lib "eagle-import") (part "C-EUC0603"))
    )
    (comp (ref "DIP21")
      (value "MULTICOMP")
      (footprint "eagle-import:MULTICOMP")
      (libsource (lib "eagle-import") (part "MULTICOMP"))
    )
    (comp (ref "IC2-1")
      (value "MCP2551-E/SN or SN65HVD230D")
      (footprint "eagle-import:SOIC127P600X175-8N")
      (fields (field (name "MPN") "MCP2551-E/SN") (field (name "MF") "MICROCHIP"))
      (libsource (lib "eagle-import") (part "MCP2551-E/SN"))
    )
    (comp (ref "IC2-2")
      (value "J-LINK-10PIN-HOLES")
      (footprint "eagle-import:J-LINK-10PIN-HOLES")
      (libsource (lib "eagle-import") (part "J-LINK-10PIN-HOLES"))
    )
    (comp (ref "IC2-3")
      (value "PRTR5V0U4D")
      (footprint "eagle-import:SC74")
      (fields (field (name "MF") "NXP") (field (name "MPN") "PRTR5V0U4D,125."))
      (libsource (lib "eagle-import") (part "PRTR5V0U4D"))
    )
    (comp (ref "JP2-1")
      (value "JP1E")
      (footprint "eagle-import:JP1")
      (libsource (lib "eagle-import") (part "JP1E"))
    )
    (comp (ref "JP2-2")
      (value "JP4E")
      (footprint "eagle-import:JP4")
      (libsource (lib "eagle-import") (part "JP4E"))
    )
    (comp (ref "R2-1")
      (value "0R")
      (footprint "eagle-import:R0603")
      (libsource (lib "eagle-import") (part "R-EU_R0603"))
    )
    (comp (ref "R2-2")
      (value "10k-100k")
      (footprint "eagle-import:R0603")
      (libsource (lib "eagle-import") (part "R-EU_R0603"))
    )
    (comp (ref "R2-3")
      (value "0R")
      (footprint "eagle-import:R0603")
      (libsource (lib "eagle-import") (part "R-EU_R0603"))
    )
    (comp (ref "R2-4")
      (value "120R")
      (footprint "eagle-import:R0603")
      (libsource (lib "eagle-import") (part "R-EU_R0603"))
    )
    (comp (ref "R2-5")
      (value "10k")
      (footprint "eagle-import:R0603")
      (libsource (lib "eagle-import") (part "R-EU_R0603"))
    )
    (comp (ref "R2-6")
      (value "10k")
      (footprint "eagle-import:R0603")
      (libsource (lib "eagle-import") (part "R-EU_R0603"))
    )
    (comp (ref "R2-7")
      (value "10k")
      (footprint "eagle-import:R0603")
      (libsource (lib "eagle-import") (part "R-EU_R0603"))
    )
    (comp (ref "R2-8")
      (value "10k")
      (footprint "eagle-import:R0603")
      (libsource (lib "eagle-import") (part "R-EU_R0603"))
    )
    (comp (ref "R2-9")
      (value "1k")
      (footprint "eagle-import:R0603")
      (libsource (lib "eagle-import") (part "R-EU_R0603"))
    )
    (comp (ref "R2-10")
      (value "1k")
      (footprint "eagle-import:R0603")
      (libsource (lib "eagle-import") (part "R-EU_R0603"))
    )
    (comp (ref "SJ2-1")
      (value "SJ2W")
      (footprint "eagle-import:SJ_2")
      (libsource (lib "eagle-import") (part "SJ2W"))
    )
  )
  (nets
    (net (code "1") (name "+3V3") (class "Default")
      (node (ref "C1-1") (pin "1") (pinfunction "1_1") (pintype "passive"))
      (node (ref "C1-2") (pin "1") (pinfunction "1_1") (pintype "passive"))
      (node (ref "C1-3") (pin "1") (pinfunction "1_1") (pintype "passive"))
      (node (ref "C1-4") (pin "1") (pinfunction "1_1") (pintype "passive"))
      (node (ref "C1-8") (pin "1") (pinfunction "1_1") (pintype "passive"))
      (node (ref "C1-9") (pin "1") (pinfunction "1_1") (pintype "passive"))
      (node (ref "C2-2") (pin "1") (pinfunction "1_1") (pintype "passive"))
      (node (ref "C3-5") (pin "1") (pinfunction "1_1") (pintype "passive"))
      (node (ref "C5-3") (pin "1") (pinfunction "1_1") (pintype "passive"))
      (node (ref "C5-4") (pin "1") (pinfunction "1_1") (pintype "passive"))
      (node (ref "C5-5") (pin "1") (pinfunction "1_1") (pintype "passive"))
      (node (ref "C5-6") (pin "1") (pinfunction "1_1") (pintype "passive"))
      (node (ref "C6-2") (pin "1") (pinfunction "1_1") (pintype "passive"))
      (node (ref "C6-3") (pin "1") (pinfunction "1_1") (pintype "passive"))
      (node (ref "IC1-1") (pin "13") (pinfunction "VDDA_13") (pintype "power_in"))
      (node (ref "IC1-1") (pin "19") (pinfunction "VDD_4_19") (pintype "power_in"))
      (node (ref "IC1-1") (pin "32") (pinfunction "VDD_1_32") (pintype "power_in"))
      (node (ref "IC1-1") (pin "48") (pinfunction "VDD_2_48") (pintype "power_in"))
      (node (ref "IC1-1") (pin "64") (pinfunction "VDD_3_64") (pintype "power_in"))
      (node (ref "IC2-2") (pin "1") (pinfunction "VTREF_1") (pintype "bidirectional"))
      (node (ref "IC2-3") (pin "5") (pinfunction "VCC_5") (pintype "power_in"))
      (node (ref "IC3-2") (pin "3") (pinfunction "OUT_3") (pintype "passive"))
      (node (ref "IC5-1") (pin "19") (pinfunction "DVDD_19") (pintype "power_in"))
      (node (ref "IC5-1") (pin "20") (pinfunction "VDD_20") (pintype "power_in"))
      (node (ref "IC5-2") (pin "19") (pinfunction "DVDD_19") (pintype "power_in"))
      (node (ref "IC5-2") (pin "20") (pinfunction "VDD_20") (pintype "power_in"))
      (node (ref "IC6-1") (pin "19") (pinfunction "DVDD_19") (pintype "power_in"))
      (node (ref "IC6-1") (pin "20") (pinfunction "VDD_20") (pintype "power_in"))
      (node (ref "JP2-2") (pin "4") (pinfunction "4_4") (pintype "passive"))
      (node (ref "R2-10") (pin "2") (pinfunction "2_2") (pintype "passive"))
      (node (ref "R2-5") (pin "2") (pinfunction "2_2") (pintype "passive"))
      (node (ref "R2-6") (pin "2") (pinfunction "2_2") (pintype "passive"))
      (node (ref "R2-7") (pin "2") (pinfunction "2_2") (pintype "passive"))
      (node (ref "R2-8") (pin "2") (pinfunction "2_2") (pintype "passive"))
      (node (ref "R2-9") (pin "2") (pinfunction "2_2") (pintype "passive"))
      (node (ref "SJ2-1") (pin "3") (pinfunction "3_3") (pintype "passive"))
    )
    (net (code "2") (name "+5V") (class "Default")
      (node (ref "C3-4") (pin "1") (pinfunction "1_1") (pintype "passive"))
      (node (ref "D3-3") (pin "C") (pinfunction "C_C") (pintype "passive"))
      (node (ref "IC3-2") (pin "1") (pinfunction "IN_1") (pintype "input"))
      (node (ref "JP3-1") (pin "2") (pinfunction "2_2") (pintype "passive"))
      (node (ref "SJ2-1") (pin "1") (pinfunction "1_1") (pintype "passive"))
      (node (ref "U$2") (pin "A1") (pinfunction "A1_A1") (pintype "bidirectional"))
    )
    (net (code "3") (name "+24V") (class "Default")
      (node (ref "C3-1") (pin "1") (pinfunction "1_1") (pintype "passive"))
      (node (ref "C3-2") (pin "1") (pinfunction "1_1") (pintype "passive"))
      (node (ref "D3-1") (pin "C") (pinfunction "C_C") (pintype "passive"))
      (node (ref "D3-2") (pin "C") (pinfunction "C_C") (pintype "passive"))
      (node (ref "IC3-1") (pin "2") (pinfunction "+VIN_2") (pintype "passive"))
      (node (ref "VAR3-2") (pin "2") (pinfunction "2_2") (pintype "passive"))
      (node (ref "VAR3-3") (pin "2") (pinfunction "2_2") (pintype "passive"))
    )
    (net (code "4") (name "C0") (class "Default")
      (node (ref "DIP21") (pin "P$8") (pinfunction "P$8_P$8") (pintype "bidirectional"))
      (node (ref "IC1-1") (pin "45") (pinfunction "PA12_45") (pintype "bidirectional"))
    )
    (net (code "5") (name "C1") (class "Default")
      (node (ref "DIP21") (pin "P$7") (pinfunction "P$7_P$7") (pintype "bidirectional"))
      (node (ref "IC1-1") (pin "44") (pinfunction "PA11_44") (pintype "bidirectional"))
    )
    (net (code "6") (name "C2") (class "Default")
      (node (ref "DIP21") (pin "P$6") (pinfunction "P$6_P$6") (pintype "bidirectional"))
      (node (ref "IC1-1") (pin "43") (pinfunction "PA10_43") (pintype "bidirectional"))
    )
    (net (code "7") (name "C3") (class "Default")
      (node (ref "DIP21") (pin "P$5") (pinfunction "P$5_P$5") (pintype "bidirectional"))
      (node (ref "IC1-1") (pin "42") (pinfunction "PA9_42") (pintype "bidirectional"))
    )
    (net (code "8") (name "C4") (class "Default")
      (node (ref "DIP21") (pin "P$4") (pinfunction "P$4_P$4") (pintype "bidirectional"))
      (node (ref "IC1-1") (pin "41") (pinfunction "PA8_41") (pintype "bidirectional"))
    )
    (net (code "9") (name "C5") (class "Default")
      (node (ref "DIP21") (pin "P$3") (pinfunction "P$3_P$3") (pintype "bidirectional"))
      (node (ref "IC1-1") (pin "40") (pinfunction "PC9_40") (pintype "bidirectional"))
    )
    (net (code "10") (name "C6") (class "Default")
      (node (ref "DIP21") (pin "P$2") (pinfunction "P$2_P$2") (pintype "bidirectional"))
      (node (ref "IC1-1") (pin "39") (pinfunction "PC8_39") (pintype "bidirectional"))
    )
    (net (code "11") (name "C7") (class "Default")
      (node (ref "DIP21") (pin "P$1") (pinfunction "1_P$1") (pintype "bidirectional"))
      (node (ref "IC1-1") (pin "38") (pinfunction "PC7_38") (pintype "bidirectional"))
    )
    (net (code "12") (name "CANH") (class "Default")
      (node (ref "IC2-1") (pin "7") (pinfunction "CANH_7") (pintype "output"))
      (node (ref "R2-4") (pin "2") (pinfunction "2_2") (pintype "passive"))
      (node (ref "SJ2") (pin "1") (pinfunction "1_1") (pintype "passive"))
      (node (ref "SJ4-2") (pin "2") (pinfunction "2_2") (pintype "passive"))
      (node (ref "U4") (pin "9") (pinfunction ".2_9") (pintype "bidirectional"))
    )
    (net (code "13") (name "CANL") (class "Default")
      (node (ref "IC2-1") (pin "6") (pinfunction "CANL_6") (pintype "output"))
      (node (ref "JP2-1") (pin "2") (pinfunction "2_2") (pintype "passive"))
      (node (ref "SJ1") (pin "1") (pinfunction "1_1") (pintype "passive"))
      (node (ref "SJ4-1") (pin "2") (pinfunction "2_2") (pintype "passive"))
      (node (ref "U4") (pin "10") (pinfunction ".1_10") (pintype "bidirectional"))
    )
    (net (code "14") (name "CAN_RX") (class "Default")
      (node (ref "IC1-1") (pin "61") (pinfunction "PB8_61") (pintype "bidirectional"))
      (node (ref "R2-3") (pin "1") (pinfunction "1_1") (pintype "passive"))
    )
    (net (code "15") (name "CAN_TX") (class "Default")
      (node (ref "IC1-1") (pin "62") (pinfunction "PB9_62") (pintype "bidirectional"))
      (node (ref "R2-1") (pin "2") (pinfunction "2_2") (pintype "passive"))
    )
    (net (code "16") (name "CS_1") (class "Default")
      (node (ref "IC1-1") (pin "23") (pinfunction "PA7_23") (pintype "bidirectional"))
      (node (ref "IC5-1") (pin "13") (pinfunction "*CS_13") (pintype "passive"))
    )
    (net (code "17") (name "CS_2") (class "Default")
      (node (ref "IC1-1") (pin "25") (pinfunction "PC5_25") (pintype "bidirectional"))
      (node (ref "IC5-2") (pin "13") (pinfunction "*CS_13") (pintype "passive"))
    )
    (net (code "18") (name "CS_3") (class "Default")
      (node (ref "IC1-1") (pin "27") (pinfunction "PB1_27") (pintype "bidirectional"))
      (node (ref "IC6-1") (pin "13") (pinfunction "*CS_13") (pintype "passive"))
    )
    (net (code "19") (name "DRDY_1") (class "Default")
      (node (ref "IC1-1") (pin "22") (pinfunction "PA6_22") (pintype "bidirectional"))
      (node (ref "IC5-1") (pin "18") (pinfunction "*DRDY_18") (pintype "passive"))
    )
    (net (code "20") (name "DRDY_2") (class "Default")
      (node (ref "IC1-1") (pin "24") (pinfunction "PC4_24") (pintype "bidirectional"))
      (node (ref "IC5-2") (pin "18") (pinfunction "*DRDY_18") (pintype "passive"))
    )
    (net (code "21") (name "DRDY_3") (class "Default")
      (node (ref "IC1-1") (pin "26") (pinfunction "PB0_26") (pintype "bidirectional"))
      (node (ref "IC6-1") (pin "18") (pinfunction "*DRDY_18") (pintype "passive"))
    )
    (net (code "22") (name "GND") (class "Default")
      (node (ref "C1-1") (pin "2") (pinfunction "2_2") (pintype "passive"))
      (node (ref "C1-10") (pin "1") (pinfunction "1_1") (pintype "passive"))
      (node (ref "C1-11") (pin "1") (pinfunction "1_1") (pintype "passive"))
      (node (ref "C1-2") (pin "2") (pinfunction "2_2") (pintype "passive"))
      (node (ref "C1-3") (pin "2") (pinfunction "2_2") (pintype "passive"))
      (node (ref "C1-4") (pin "2") (pinfunction "2_2") (pintype "passive"))
      (node (ref "C1-5") (pin "2") (pinfunction "2_2") (pintype "passive"))
      (node (ref "C1-6") (pin "1") (pinfunction "1_1") (pintype "passive"))
      (node (ref "C1-7") (pin "1") (pinfunction "1_1") (pintype "passive"))
      (node (ref "C1-8") (pin "2") (pinfunction "2_2") (pintype "passive"))
      (node (ref "C1-9") (pin "2") (pinfunction "2_2") (pintype "passive"))
      (node (ref "C2-1") (pin "2") (pinfunction "2_2") (pintype "passive"))
      (node (ref "C2-2") (pin "2") (pinfunction "2_2") (pintype "passive"))
      (node (ref "C3-3") (pin "2") (pinfunction "2_2") (pintype "passive"))
      (node (ref "C3-4") (pin "2") (pinfunction "2_2") (pintype "passive"))
      (node (ref "C3-5") (pin "2") (pinfunction "2_2") (pintype "passive"))
      (node (ref "C5-3") (pin "2") (pinfunction "2_2") (pintype "passive"))
      (node (ref "C5-4") (pin "2") (pinfunction "2_2") (pintype "passive"))
      (node (ref "C5-5") (pin "2") (pinfunction "2_2") (pintype "passive"))
      (node (ref "C5-6") (pin "2") (pinfunction "2_2") (pintype "passive"))
      (node (ref "C6-2") (pin "2") (pinfunction "2_2") (pintype "passive"))
      (node (ref "C6-3") (pin "2") (pinfunction "2_2") (pintype "passive"))
      (node (ref "D5-1") (pin "3") (pinfunction "3_3") (pintype "passive"))
      (node (ref "D5-2") (pin "3") (pinfunction "3_3") (pintype "passive"))
      (node (ref "D6-1") (pin "3") (pinfunction "3_3") (pintype "passive"))
      (node (ref "DIP21") (pin "P$10") (pinfunction "P$10_P$10") (pintype "bidirectional"))
      (node (ref "DIP21") (pin "P$11") (pinfunction "P$11_P$11") (pintype "bidirectional"))
      (node (ref "DIP21") (pin "P$12") (pinfunction "P$12_P$12") (pintype "bidirectional"))
      (node (ref "DIP21") (pin "P$13") (pinfunction "P$13_P$13") (pintype "bidirectional"))
      (node (ref "DIP21") (pin "P$14") (pinfunction "P$14_P$14") (pintype "bidirectional"))
      (node (ref "DIP21") (pin "P$15") (pinfunction "P$15_P$15") (pintype "bidirectional"))
      (node (ref "DIP21") (pin "P$16") (pinfunction "P$16_P$16") (pintype "bidirectional"))
      (node (ref "DIP21") (pin "P$9") (pinfunction "P$9_P$9") (pintype "bidirectional"))
      (node (ref "IC1-1") (pin "12") (pinfunction "VSSA_12") (pintype "power_in"))
      (node (ref "IC1-1") (pin "18") (pinfunction "VSS_4_18") (pintype "power_in"))
      (node (ref "IC1-1") (pin "31") (pinfunction "VSS_1_31") (pintype "power_in"))
      (node (ref "IC1-1") (pin "47") (pinfunction "VSS_2_47") (pintype "power_in"))
      (node (ref "IC1-1") (pin "60") (pinfunction "BOOT0_60") (pintype "input"))
      (node (ref "IC1-1") (pin "63") (pinfunction "VSS_3_63") (pintype "power_in"))
      (node (ref "IC2-1") (pin "2") (pinfunction "VSS_2") (pintype "power_in"))
      (node (ref "IC2-2") (pin "3") (pinfunction "GND_3") (pintype "bidirectional"))
      (node (ref "IC2-3") (pin "2") (pinfunction "GND_2") (pintype "power_in"))
      (node (ref "IC3-1") (pin "3") (pinfunction "-VOUT_3") (pintype "passive"))
      (node (ref "IC3-2") (pin "2") (pinfunction "GND_2") (pintype "input"))
      (node (ref "IC3-2") (pin "4") (pinfunction "GND_4") (pintype "input"))
      (node (ref "IC5-1") (pin "10") (pinfunction "GND2_10") (pintype "power_in"))
      (node (ref "IC5-1") (pin "15") (pinfunction "DGND_15") (pintype "power_in"))
      (node (ref "IC5-1") (pin "16") (pinfunction "GND1_16") (pintype "power_in"))
      (node (ref "IC5-1") (pin "21") (pinfunction "21_21") (pintype "passive"))
      (node (ref "IC5-1") (pin "6") (pinfunction "FORCE2_6") (pintype "passive"))
      (node (ref "IC5-2") (pin "10") (pinfunction "GND2_10") (pintype "power_in"))
      (node (ref "IC5-2") (pin "15") (pinfunction "DGND_15") (pintype "power_in"))
      (node (ref "IC5-2") (pin "16") (pinfunction "GND1_16") (pintype "power_in"))
      (node (ref "IC5-2") (pin "21") (pinfunction "21_21") (pintype "passive"))
      (node (ref "IC5-2") (pin "6") (pinfunction "FORCE2_6") (pintype "passive"))
      (node (ref "IC6-1") (pin "10") (pinfunction "GND2_10") (pintype "power_in"))
      (node (ref "IC6-1") (pin "15") (pinfunction "DGND_15") (pintype "power_in"))
      (node (ref "IC6-1") (pin "16") (pinfunction "GND1_16") (pintype "power_in"))
      (node (ref "IC6-1") (pin "21") (pinfunction "21_21") (pintype "passive"))
      (node (ref "IC6-1") (pin "6") (pinfunction "FORCE2_6") (pintype "passive"))
      (node (ref "JP2-2") (pin "1") (pinfunction "1_1") (pintype "passive"))
      (node (ref "LED1-1") (pin "C") (pinfunction "C_C") (pintype "passive"))
      (node (ref "R2-2") (pin "2") (pinfunction "2_2") (pintype "passive"))
      (node (ref "RTC_HOUSING_GND") (pin "TP") (pinfunction "TP_TP") (pintype "input"))
      (node (ref "S1-1") (pin "1") (pinfunction "P_1") (pintype "passive"))
      (node (ref "T3-1") (pin "3") (pinfunction "E_3") (pintype "passive"))
      (node (ref "TP3-2") (pin "MP") (pinfunction "MP_MP") (pintype "passive"))
      (node (ref "U4") (pin "33") (pinfunction "B3_33") (pintype "bidirectional"))
      (node (ref "U4") (pin "37") (pinfunction "B7_37") (pintype "bidirectional"))
    )
    (net (code "23") (name "GND1") (class "Default")
      (node (ref "C3-1") (pin "2") (pinfunction "2_2") (pintype "passive"))
      (node (ref "C3-2") (pin "2") (pinfunction "2_2") (pintype "passive"))
      (node (ref "D3-2") (pin "A") (pinfunction "A_A") (pintype "passive"))
      (node (ref "IC3-1") (pin "1") (pinfunction "-VIN_1") (pintype "passive"))
      (node (ref "U4") (pin "13") (pinfunction ".2_13") (pintype "bidirectional"))
      (node (ref "U4") (pin "14") (pinfunction ".1_14") (pintype "bidirectional"))
      (node (ref "VAR3-1") (pin "1") (pinfunction "1_1") (pintype "passive"))
      (node (ref "VAR3-2") (pin "1") (pinfunction "1_1") (pintype "passive"))
    )
    (net (code "24") (name "I2C1_SCL") (class "Default")
      (node (ref "IC1-1") (pin "58") (pinfunction "PB6_58") (pintype "bidirectional"))
      (node (ref "IC2-3") (pin "1") (pinfunction "IO1_1") (pintype "passive"))
      (node (ref "R2-9") (pin "1") (pinfunction "1_1") (pintype "passive"))
      (node (ref "SJ4-3") (pin "2") (pinfunction "2_2") (pintype "passive"))
    )
    (net (code "25") (name "I2C1_SDA") (class "Default")
      (node (ref "IC1-1") (pin "59") (pinfunction "PB7_59") (pintype "bidirectional"))
      (node (ref "IC2-3") (pin "6") (pinfunction "IO4_6") (pintype "passive"))
      (node (ref "R2-10") (pin "1") (pinfunction "1_1") (pintype "passive"))
      (node (ref "SJ4-4") (pin "2") (pinfunction "2_2") (pintype "passive"))
    )
    (net (code "26") (name "I2C1_SMBA") (class "Default")
      (node (ref "IC1-1") (pin "57") (pinfunction "PB5_57") (pintype "bidirectional"))
      (node (ref "IC2-3") (pin "4") (pinfunction "IO3_4") (pintype "passive"))
    )
    (net (code "27") (name "JTAG_SUPPLY") (class "Default")
      (node (ref "IC2-2") (pin "5") (pinfunction "5V-SUPPLY_5") (pintype "bidirectional"))
      (node (ref "JP3-1") (pin "1") (pinfunction "1_1") (pintype "passive"))
    )
    (net (code "28") (name "JTAG_TCK") (class "Default")
      (node (ref "IC1-1") (pin "49") (pinfunction "PA14_49") (pintype "bidirectional"))
      (node (ref "IC2-2") (pin "4") (pinfunction "SWCLK/TCK_4") (pintype "bidirectional"))
    )
    (net (code "29") (name "JTAG_TDI") (class "Default")
      (node (ref "IC1-1") (pin "50") (pinfunction "PA15_50") (pintype "bidirectional"))
      (node (ref "IC2-2") (pin "8") (pinfunction "TDI_8") (pintype "bidirectional"))
      (node (ref "R2-6") (pin "1") (pinfunction "1_1") (pintype "passive"))
    )
    (net (code "30") (name "JTAG_TDO") (class "Default")
      (node (ref "IC1-1") (pin "55") (pinfunction "PB3_55") (pintype "bidirectional"))
      (node (ref "IC2-2") (pin "6") (pinfunction "SWO/TDO_6") (pintype "bidirectional"))
      (node (ref "R2-5") (pin "1") (pinfunction "1_1") (pintype "passive"))
    )
    (net (code "31") (name "JTAG_TMS") (class "Default")
      (node (ref "IC1-1") (pin "46") (pinfunction "PA13_46") (pintype "bidirectional"))
      (node (ref "IC2-2") (pin "2") (pinfunction "SWDIO/TMS_2") (pintype "bidirectional"))
      (node (ref "R2-8") (pin "1") (pinfunction "1_1") (pintype "passive"))
    )
    (net (code "32") (name "JTAG_TRST") (class "Default")
      (node (ref "IC1-1") (pin "56") (pinfunction "PB4_56") (pintype "bidirectional"))
      (node (ref "IC2-2") (pin "9") (pinfunction "TRST_9") (pintype "bidirectional"))
      (node (ref "R2-7") (pin "1") (pinfunction "1_1") (pintype "passive"))
    )
    (net (code "33") (name "LED1") (class "Default")
      (node (ref "IC1-1") (pin "21") (pinfunction "PA5_21") (pintype "bidirectional"))
      (node (ref "R1-3") (pin "1") (pinfunction "1_1") (pintype "passive"))
    )
    (net (code "34") (name "LED2") (class "Default")
      (node (ref "IC1-1") (pin "20") (pinfunction "PA4_20") (pintype "bidirectional"))
      (node (ref "R1-4") (pin "1") (pinfunction "1_1") (pintype "passive"))
    )
    (net (code "35") (name "NRST") (class "Default")
      (node (ref "C1-5") (pin "1") (pinfunction "1_1") (pintype "passive"))
      (node (ref "IC1-1") (pin "7") (pinfunction "NRST_7") (pintype "input"))
      (node (ref "IC2-2") (pin "10") (pinfunction "NRESET_10") (pintype "bidirectional"))
      (node (ref "S1-1") (pin "2") (pinfunction "S_2") (pintype "passive"))
    )
    (net (code "36") (name "Net-(D3-1-PadA)") (class "Default")
      (node (ref "D3-1") (pin "A") (pinfunction "A_A") (pintype "passive"))
      (node (ref "F3-1") (pin "1") (pinfunction "1_1") (pintype "passive"))
      (node (ref "F3-2") (pin "1A") (pinfunction "1A_1A") (pintype "passive"))
    )
    (net (code "37") (name "Net-(IC1-1H-PD0{slash}OSC<=)") (class "Default")
      (node (ref "C1-6") (pin "2") (pinfunction "2_2") (pintype "passive"))
      (node (ref "IC1-1") (pin "5") (pinfunction "PD0/OSC<=_5") (pintype "bidirectional"))
      (node (ref "Q1-1") (pin "2") (pinfunction "2_2") (pintype "bidirectional"))
      (node (ref "R1-1") (pin "2") (pinfunction "2_2") (pintype "passive"))
    )
    (net (code "38") (name "Net-(IC1-1H-PD1{slash}OSC=>)") (class "Default")
      (node (ref "C1-7") (pin "2") (pinfunction "2_2") (pintype "passive"))
      (node (ref "IC1-1") (pin "6") (pinfunction "PD1/OSC=>_6") (pintype "bidirectional"))
      (node (ref "Q1-1") (pin "1") (pinfunction "1_1") (pintype "bidirectional"))
      (node (ref "R1-1") (pin "1") (pinfunction "1_1") (pintype "passive"))
    )
    (net (code "39") (name "Net-(IC2-1-RS)") (class "Default")
      (node (ref "IC2-1") (pin "8") (pinfunction "RS_8") (pintype "input"))
      (node (ref "R2-2") (pin "1") (pinfunction "1_1") (pintype "passive"))
    )
    (net (code "40") (name "Net-(IC2-1-RXD)") (class "Default")
      (node (ref "IC2-1") (pin "4") (pinfunction "RXD_4") (pintype "output"))
      (node (ref "R2-3") (pin "2") (pinfunction "2_2") (pintype "passive"))
    )
    (net (code "41") (name "Net-(IC2-1-TXD)") (class "Default")
      (node (ref "IC2-1") (pin "1") (pinfunction "TXD_1") (pintype "input"))
      (node (ref "R2-1") (pin "1") (pinfunction "1_1") (pintype "passive"))
    )
    (net (code "42") (name "Net-(IC2-1-VDD)") (class "Default")
      (node (ref "C2-1") (pin "1") (pinfunction "1_1") (pintype "passive"))
      (node (ref "IC2-1") (pin "3") (pinfunction "VDD_3") (pintype "power_in"))
      (node (ref "SJ2-1") (pin "2") (pinfunction "2_2") (pintype "passive"))
    )
    (net (code "43") (name "Net-(IC3-1-+VOUT)") (class "Default")
      (node (ref "C3-3") (pin "1") (pinfunction "1_1") (pintype "passive"))
      (node (ref "IC3-1") (pin "4") (pinfunction "+VOUT_4") (pintype "passive"))
      (node (ref "JP3-1") (pin "3") (pinfunction "3_3") (pintype "passive"))
      (node (ref "TP3-1") (pin "MP") (pinfunction "MP_MP") (pintype "passive"))
    )
    (net (code "44") (name "Net-(IC5-1-BIAS)") (class "Default")
      (node (ref "IC5-1") (pin "1") (pinfunction "BIAS_1") (pintype "passive"))
      (node (ref "IC5-1") (pin "2") (pinfunction "REFIN+_2") (pintype "passive"))
      (node (ref "R5-1") (pin "2") (pinfunction "2_2") (pintype "passive"))
    )
    (net (code "45") (name "Net-(IC5-1-ISENSOR)") (class "Default")
      (node (ref "IC5-1") (pin "3") (pinfunction "REFIN-_3") (pintype "passive"))
      (node (ref "IC5-1") (pin "4") (pinfunction "ISENSOR_4") (pintype "passive"))
      (node (ref "R5-1") (pin "1") (pinfunction "1_1") (pintype "passive"))
    )
    (net (code "46") (name "Net-(IC5-2-BIAS)") (class "Default")
      (node (ref "IC5-2") (pin "1") (pinfunction "BIAS_1") (pintype "passive"))
      (node (ref "IC5-2") (pin "2") (pinfunction "REFIN+_2") (pintype "passive"))
      (node (ref "R5-2") (pin "2") (pinfunction "2_2") (pintype "passive"))
    )
    (net (code "47") (name "Net-(IC5-2-ISENSOR)") (class "Default")
      (node (ref "IC5-2") (pin "3") (pinfunction "REFIN-_3") (pintype "passive"))
      (node (ref "IC5-2") (pin "4") (pinfunction "ISENSOR_4") (pintype "passive"))
      (node (ref "R5-2") (pin "1") (pinfunction "1_1") (pintype "passive"))
    )
    (net (code "48") (name "Net-(IC6-1-BIAS)") (class "Default")
      (node (ref "IC6-1") (pin "1") (pinfunction "BIAS_1") (pintype "passive"))
      (node (ref "IC6-1") (pin "2") (pinfunction "REFIN+_2") (pintype "passive"))
      (node (ref "R6-1") (pin "2") (pinfunction "2_2") (pintype "passive"))
    )
    (net (code "49") (name "Net-(IC6-1-ISENSOR)") (class "Default")
      (node (ref "IC6-1") (pin "3") (pinfunction "REFIN-_3") (pintype "passive"))
      (node (ref "IC6-1") (pin "4") (pinfunction "ISENSOR_4") (pintype "passive"))
      (node (ref "R6-1") (pin "1") (pinfunction "1_1") (pintype "passive"))
    )
    (net (code "50") (name "Net-(JP2-1-Pad1)") (class "Default")
      (node (ref "JP2-1") (pin "1") (pinfunction "1_1") (pintype "passive"))
      (node (ref "R2-4") (pin "1") (pinfunction "1_1") (pintype "passive"))
    )
    (net (code "51") (name "Net-(LED1-1-AG)") (class "Default")
      (node (ref "LED1-1") (pin "AX") (pinfunction "AG_AX") (pintype "passive"))
      (node (ref "R1-4") (pin "2") (pinfunction "2_2") (pintype "passive"))
    )
    (net (code "52") (name "Net-(LED1-1-PadAR)") (class "Default")
      (node (ref "LED1-1") (pin "AR") (pinfunction "AR_AR") (pintype "passive"))
      (node (ref "R1-3") (pin "2") (pinfunction "2_2") (pintype "passive"))
    )
    (net (code "53") (name "Net-(T3-1-C)") (class "Default")
      (node (ref "D3-3") (pin "A") (pinfunction "A_A") (pintype "passive"))
      (node (ref "T3-1") (pin "1") (pinfunction "C_1") (pintype "passive"))
      (node (ref "U$2") (pin "A2") (pinfunction "A2_A2") (pintype "bidirectional"))
    )
    (net (code "54") (name "Net-(U4A-B1)") (class "Default")
      (node (ref "SJ4-1") (pin "1") (pinfunction "1_1") (pintype "passive"))
      (node (ref "U4") (pin "31") (pinfunction "B1_31") (pintype "bidirectional"))
    )
    (net (code "55") (name "Net-(U4A-B2)") (class "Default")
      (node (ref "SJ4-2") (pin "1") (pinfunction "1_1") (pintype "passive"))
      (node (ref "U4") (pin "32") (pinfunction "B2_32") (pintype "bidirectional"))
    )
    (net (code "56") (name "Net-(U4A-B5)") (class "Default")
      (node (ref "SJ4-3") (pin "1") (pinfunction "1_1") (pintype "passive"))
      (node (ref "U4") (pin "35") (pinfunction "B5_35") (pintype "bidirectional"))
    )
    (net (code "57") (name "Net-(U4A-B6)") (class "Default")
      (node (ref "SJ4-4") (pin "1") (pinfunction "1_1") (pintype "passive"))
      (node (ref "U4") (pin "36") (pinfunction "B6_36") (pintype "bidirectional"))
    )
    (net (code "58") (name "Net-(U4A-B8)") (class "Default")
      (node (ref "TP4-3") (pin "MP") (pinfunction "MP_MP") (pintype "passive"))
      (node (ref "U4") (pin "38") (pinfunction "B8_38") (pintype "bidirectional"))
    )
    (net (code "59") (name "Net-(U4A-B9)") (class "Default")
      (node (ref "TP4-2") (pin "MP") (pinfunction "MP_MP") (pintype "passive"))
      (node (ref "U4") (pin "39") (pinfunction "B9_39") (pintype "bidirectional"))
    )
    (net (code "60") (name "Net-(U4A-B10)") (class "Default")
      (node (ref "TP4-1") (pin "MP") (pinfunction "MP_MP") (pintype "passive"))
      (node (ref "U4") (pin "40") (pinfunction "B10_40") (pintype "bidirectional"))
    )
    (net (code "61") (name "Net-(U4C-.3)") (class "Default")
      (node (ref "SJ1") (pin "2") (pinfunction "2_2") (pintype "passive"))
      (node (ref "U4") (pin "11") (pinfunction ".3_11") (pintype "bidirectional"))
    )
    (net (code "62") (name "Net-(U4C-.4)") (class "Default")
      (node (ref "SJ2") (pin "2") (pinfunction "2_2") (pintype "passive"))
      (node (ref "U4") (pin "12") (pinfunction ".4_12") (pintype "bidirectional"))
    )
    (net (code "63") (name "OSC32_IN") (class "Default")
      (node (ref "C1-10") (pin "2") (pinfunction "2_2") (pintype "passive"))
      (node (ref "IC1-1") (pin "3") (pinfunction "PC14_3") (pintype "bidirectional"))
      (node (ref "Q1-2") (pin "P$1") (pinfunction "1_P$1") (pintype "bidirectional"))
      (node (ref "R1-2") (pin "2") (pinfunction "2_2") (pintype "passive"))
    )
    (net (code "64") (name "OSC32_OUT") (class "Default")
      (node (ref "C1-11") (pin "2") (pinfunction "2_2") (pintype "passive"))
      (node (ref "IC1-1") (pin "4") (pinfunction "PC15_4") (pintype "bidirectional"))
      (node (ref "Q1-2") (pin "P$2") (pinfunction "2_P$2") (pintype "bidirectional"))
      (node (ref "R1-2") (pin "1") (pinfunction "1_1") (pintype "passive"))
    )
    (net (code "65") (name "PE") (class "Default")
      (node (ref "U4") (pin "41") (pinfunction "PE_41") (pintype "bidirectional"))
      (node (ref "VAR3-1") (pin "2") (pinfunction "2_2") (pintype "passive"))
      (node (ref "VAR3-3") (pin "1") (pinfunction "1_1") (pintype "passive"))
    )
    (net (code "66") (name "RELAIS_COM") (class "Default")
      (node (ref "U$2") (pin "11") (pinfunction "11_11") (pintype "bidirectional"))
      (node (ref "U4") (pin "7") (pinfunction ".1_7") (pintype "bidirectional"))
    )
    (net (code "67") (name "RELAIS_NC") (class "Default")
      (node (ref "U$2") (pin "12") (pinfunction "12_12") (pintype "bidirectional"))
      (node (ref "U4") (pin "6") (pinfunction ".2_6") (pintype "bidirectional"))
    )
    (net (code "68") (name "RELAIS_NO") (class "Default")
      (node (ref "U$2") (pin "14") (pinfunction "13_14") (pintype "bidirectional"))
      (node (ref "U4") (pin "8") (pinfunction ".3_8") (pintype "bidirectional"))
    )
    (net (code "69") (name "RELAIS_ON") (class "Default")
      (node (ref "IC1-1") (pin "2") (pinfunction "PC13_2") (pintype "bidirectional"))
      (node (ref "T3-1") (pin "2") (pinfunction "B_2") (pintype "passive"))
    )
    (net (code "70") (name "RTD1+") (class "Default")
      (node (ref "C5-1") (pin "2") (pinfunction "2_2") (pintype "passive"))
      (node (ref "D5-1") (pin "2") (pinfunction "2_2") (pintype "passive"))
      (node (ref "IC5-1") (pin "5") (pinfunction "FORCE+_5") (pintype "passive"))
      (node (ref "IC5-1") (pin "7") (pinfunction "RTDIN+_7") (pintype "passive"))
      (node (ref "SJ1") (pin "3") (pinfunction "3_3") (pintype "passive"))
    )
    (net (code "71") (name "RTD1-") (class "Default")
      (node (ref "C5-1") (pin "1") (pinfunction "1_1") (pintype "passive"))
      (node (ref "D5-1") (pin "1") (pinfunction "1_1") (pintype "passive"))
      (node (ref "IC5-1") (pin "8") (pinfunction "RTDIN-_8") (pintype "passive"))
      (node (ref "IC5-1") (pin "9") (pinfunction "FORCE-_9") (pintype "passive"))
      (node (ref "SJ2") (pin "3") (pinfunction "3_3") (pintype "passive"))
    )
    (net (code "72") (name "RTD2+") (class "Default")
      (node (ref "C5-2") (pin "2") (pinfunction "2_2") (pintype "passive"))
      (node (ref "D5-2") (pin "2") (pinfunction "2_2") (pintype "passive"))
      (node (ref "IC5-2") (pin "5") (pinfunction "FORCE+_5") (pintype "passive"))
      (node (ref "IC5-2") (pin "7") (pinfunction "RTDIN+_7") (pintype "passive"))
      (node (ref "U4") (pin "4") (pinfunction ".3_4") (pintype "bidirectional"))
    )
    (net (code "73") (name "RTD2-") (class "Default")
      (node (ref "C5-2") (pin "1") (pinfunction "1_1") (pintype "passive"))
      (node (ref "D5-2") (pin "1") (pinfunction "1_1") (pintype "passive"))
      (node (ref "IC5-2") (pin "8") (pinfunction "RTDIN-_8") (pintype "passive"))
      (node (ref "IC5-2") (pin "9") (pinfunction "FORCE-_9") (pintype "passive"))
      (node (ref "U4") (pin "1") (pinfunction ".4_1") (pintype "bidirectional"))
    )
    (net (code "74") (name "RTD3+") (class "Default")
      (node (ref "C6-1") (pin "2") (pinfunction "2_2") (pintype "passive"))
      (node (ref "D6-1") (pin "2") (pinfunction "2_2") (pintype "passive"))
      (node (ref "IC6-1") (pin "5") (pinfunction "FORCE+_5") (pintype "passive"))
      (node (ref "IC6-1") (pin "7") (pinfunction "RTDIN+_7") (pintype "passive"))
      (node (ref "U4") (pin "3") (pinfunction ".1_3") (pintype "bidirectional"))
    )
    (net (code "75") (name "RTD3-") (class "Default")
      (node (ref "C6-1") (pin "1") (pinfunction "1_1") (pintype "passive"))
      (node (ref "D6-1") (pin "1") (pinfunction "1_1") (pintype "passive"))
      (node (ref "IC6-1") (pin "8") (pinfunction "RTDIN-_8") (pintype "passive"))
      (node (ref "IC6-1") (pin "9") (pinfunction "FORCE-_9") (pintype "passive"))
      (node (ref "U4") (pin "2") (pinfunction ".2_2") (pintype "bidirectional"))
    )
    (net (code "76") (name "SPI2_MISO") (class "Default")
      (node (ref "IC1-1") (pin "35") (pinfunction "PB14_35") (pintype "bidirectional"))
      (node (ref "IC5-1") (pin "14") (pinfunction "SDO_14") (pintype "passive"))
      (node (ref "IC5-2") (pin "14") (pinfunction "SDO_14") (pintype "passive"))
      (node (ref "IC6-1") (pin "14") (pinfunction "SDO_14") (pintype "passive"))
    )
    (net (code "77") (name "SPI2_MOSI") (class "Default")
      (node (ref "IC1-1") (pin "34") (pinfunction "PB13_34") (pintype "bidirectional"))
      (node (ref "IC5-1") (pin "11") (pinfunction "SDI_11") (pintype "passive"))
      (node (ref "IC5-2") (pin "11") (pinfunction "SDI_11") (pintype "passive"))
      (node (ref "IC6-1") (pin "11") (pinfunction "SDI_11") (pintype "passive"))
    )
    (net (code "78") (name "SPI2_SCK") (class "Default")
      (node (ref "IC1-1") (pin "36") (pinfunction "PB15_36") (pintype "bidirectional"))
      (node (ref "IC5-1") (pin "12") (pinfunction "SCLK_12") (pintype "passive"))
      (node (ref "IC5-2") (pin "12") (pinfunction "SCLK_12") (pintype "passive"))
      (node (ref "IC6-1") (pin "12") (pinfunction "SCLK_12") (pintype "passive"))
    )
    (net (code "79") (name "SUPPLY_24V") (class "Default")
      (node (ref "F3-1") (pin "2") (pinfunction "2_2") (pintype "passive"))
      (node (ref "F3-2") (pin "2A") (pinfunction "2A_2A") (pintype "passive"))
      (node (ref "U4") (pin "15") (pinfunction ".3_15") (pintype "bidirectional"))
      (node (ref "U4") (pin "16") (pinfunction ".4_16") (pintype "bidirectional"))
    )
    (net (code "80") (name "USART2_RX") (class "Default")
      (node (ref "IC1-1") (pin "17") (pinfunction "PA3_17") (pintype "bidirectional"))
      (node (ref "JP2-2") (pin "3") (pinfunction "3_3") (pintype "passive"))
    )
    (net (code "81") (name "USART2_TX") (class "Default")
      (node (ref "IC1-1") (pin "16") (pinfunction "PA2_16") (pintype "bidirectional"))
      (node (ref "JP2-2") (pin "2") (pinfunction "2_2") (pintype "passive"))
    )
    (net (code "82") (name "VBAT") (class "Default")
      (node (ref "IC1-1") (pin "1") (pinfunction "VBAT_1") (pintype "power_in"))
    )
    (net (code "83") (name "unconnected-(F3-2-Pad1B)") (class "Default")
      (node (ref "F3-2") (pin "1B") (pinfunction "1B_1B") (pintype "passive"))
    )
    (net (code "84") (name "unconnected-(F3-2-Pad2B)") (class "Default")
      (node (ref "F3-2") (pin "2B") (pinfunction "2B_2B") (pintype "passive"))
    )
    (net (code "85") (name "unconnected-(IC1-1C-PA0-Pad14)") (class "Default")
      (node (ref "IC1-1") (pin "14") (pinfunction "PA0_14") (pintype "bidirectional"))
    )
    (net (code "86") (name "unconnected-(IC1-1C-PA1-Pad15)") (class "Default")
      (node (ref "IC1-1") (pin "15") (pinfunction "PA1_15") (pintype "bidirectional"))
    )
    (net (code "87") (name "unconnected-(IC1-1D-PB10-Pad29)") (class "Default")
      (node (ref "IC1-1") (pin "29") (pinfunction "PB10_29") (pintype "bidirectional"))
    )
    (net (code "88") (name "unconnected-(IC1-1D-PB11-Pad30)") (class "Default")
      (node (ref "IC1-1") (pin "30") (pinfunction "PB11_30") (pintype "bidirectional"))
    )
    (net (code "89") (name "unconnected-(IC1-1D-PB12-Pad33)") (class "Default")
      (node (ref "IC1-1") (pin "33") (pinfunction "PB12_33") (pintype "bidirectional"))
    )
    (net (code "90") (name "unconnected-(IC1-1E-PB2-Pad28)") (class "Default")
      (node (ref "IC1-1") (pin "28") (pinfunction "PB2_28") (pintype "bidirectional"))
    )
    (net (code "91") (name "unconnected-(IC1-1F-PC10-Pad51)") (class "Default")
      (node (ref "IC1-1") (pin "51") (pinfunction "PC10_51") (pintype "bidirectional"))
    )
    (net (code "92") (name "unconnected-(IC1-1F-PC11-Pad52)") (class "Default")
      (node (ref "IC1-1") (pin "52") (pinfunction "PC11_52") (pintype "bidirectional"))
    )
    (net (code "93") (name "unconnected-(IC1-1F-PC12-Pad53)") (class "Default")
      (node (ref "IC1-1") (pin "53") (pinfunction "PC12_53") (pintype "bidirectional"))
    )
    (net (code "94") (name "unconnected-(IC1-1G-PC0-Pad8)") (class "Default")
      (node (ref "IC1-1") (pin "8") (pinfunction "PC0_8") (pintype "bidirectional"))
    )
    (net (code "95") (name "unconnected-(IC1-1G-PC1-Pad9)") (class "Default")
      (node (ref "IC1-1") (pin "9") (pinfunction "PC1_9") (pintype "bidirectional"))
    )
    (net (code "96") (name "unconnected-(IC1-1G-PC2-Pad10)") (class "Default")
      (node (ref "IC1-1") (pin "10") (pinfunction "PC2_10") (pintype "bidirectional"))
    )
    (net (code "97") (name "unconnected-(IC1-1G-PC3-Pad11)") (class "Default")
      (node (ref "IC1-1") (pin "11") (pinfunction "PC3_11") (pintype "bidirectional"))
    )
    (net (code "98") (name "unconnected-(IC1-1G-PC6-Pad37)") (class "Default")
      (node (ref "IC1-1") (pin "37") (pinfunction "PC6_37") (pintype "bidirectional"))
    )
    (net (code "99") (name "unconnected-(IC1-1H-PD2-Pad54)") (class "Default")
      (node (ref "IC1-1") (pin "54") (pinfunction "PD2_54") (pintype "bidirectional"))
    )
    (net (code "100") (name "unconnected-(IC2-1-VREF-Pad5)") (class "Default")
      (node (ref "IC2-1") (pin "5") (pinfunction "VREF_5") (pintype "input"))
    )
    (net (code "101") (name "unconnected-(IC2-2-RTCK-Pad7)") (class "Default")
      (node (ref "IC2-2") (pin "7") (pinfunction "RTCK_7") (pintype "bidirectional"))
    )
    (net (code "102") (name "unconnected-(IC2-3-IO2-Pad3)") (class "Default")
      (node (ref "IC2-3") (pin "3") (pinfunction "IO2_3") (pintype "passive"))
    )
    (net (code "103") (name "unconnected-(IC5-1-NC-Pad17)") (class "Default")
      (node (ref "IC5-1") (pin "17") (pinfunction "NC_17") (pintype "passive"))
    )
    (net (code "104") (name "unconnected-(IC5-2-NC-Pad17)") (class "Default")
      (node (ref "IC5-2") (pin "17") (pinfunction "NC_17") (pintype "passive"))
    )
    (net (code "105") (name "unconnected-(IC6-1-NC-Pad17)") (class "Default")
      (node (ref "IC6-1") (pin "17") (pinfunction "NC_17") (pintype "passive"))
    )
    (net (code "106") (name "unconnected-(U4A-B4-Pad34)") (class "Default")
      (node (ref "U4") (pin "34") (pinfunction "B4_34") (pintype "bidirectional"))
    )
    (net (code "107") (name "unconnected-(U4D-.4-Pad5)") (class "Default")
      (node (ref "U4") (pin "5") (pinfunction ".4_5") (pintype "bidirectional"))
    )
    (net (code "108") (name "unconnected-(U4F-B1-Pad17)") (class "Default")
      (node (ref "U4") (pin "17") (pinfunction "B1_17") (pintype "bidirectional"))
    )
    (net (code "109") (name "unconnected-(U4F-B2-Pad22)") (class "Default")
      (node (ref "U4") (pin "22") (pinfunction "B2_22") (pintype "bidirectional"))
    )
    (net (code "110") (name "unconnected-(U4F-B3-Pad23)") (class "Default")
      (node (ref "U4") (pin "23") (pinfunction "B3_23") (pintype "bidirectional"))
    )
    (net (code "111") (name "unconnected-(U4F-B4-Pad24)") (class "Default")
      (node (ref "U4") (pin "24") (pinfunction "B4_24") (pintype "bidirectional"))
    )
    (net (code "112") (name "unconnected-(U4F-B5-Pad25)") (class "Default")
      (node (ref "U4") (pin "25") (pinfunction "B5_25") (pintype "bidirectional"))
    )
    (net (code "113") (name "unconnected-(U4F-B6-Pad26)") (class "Default")
      (node (ref "U4") (pin "26") (pinfunction "B6_26") (pintype "bidirectional"))
    )
    (net (code "114") (name "unconnected-(U4F-B7-Pad27)") (class "Default")
      (node (ref "U4") (pin "27") (pinfunction "B7_27") (pintype "bidirectional"))
    )
    (net (code "115") (name "unconnected-(U4F-B8-Pad28)") (class "Default")
      (node (ref "U4") (pin "28") (pinfunction "B8_28") (pintype "bidirectional"))
    )
    (net (code "116") (name "unconnected-(U4F-B9-Pad29)") (class "Default")
      (node (ref "U4") (pin "29") (pinfunction "B9_29") (pintype "bidirectional"))
    )
    (net (code "117") (name "unconnected-(U4F-B10-Pad30)") (class "Default")
      (node (ref "U4") (pin "30") (pinfunction "B10_30") (pintype "bidirectional"))
    )
    (net (code "118") (name "unconnected-(U4F-PE-Pad42)") (class "Default")
      (node (ref "U4") (pin "42") (pinfunction "PE_42") (pintype "bidirectional"))
    )
  )
)
